# OPBS-Muscle.net
KiCad netlist of a schematic drawn in EAGLE
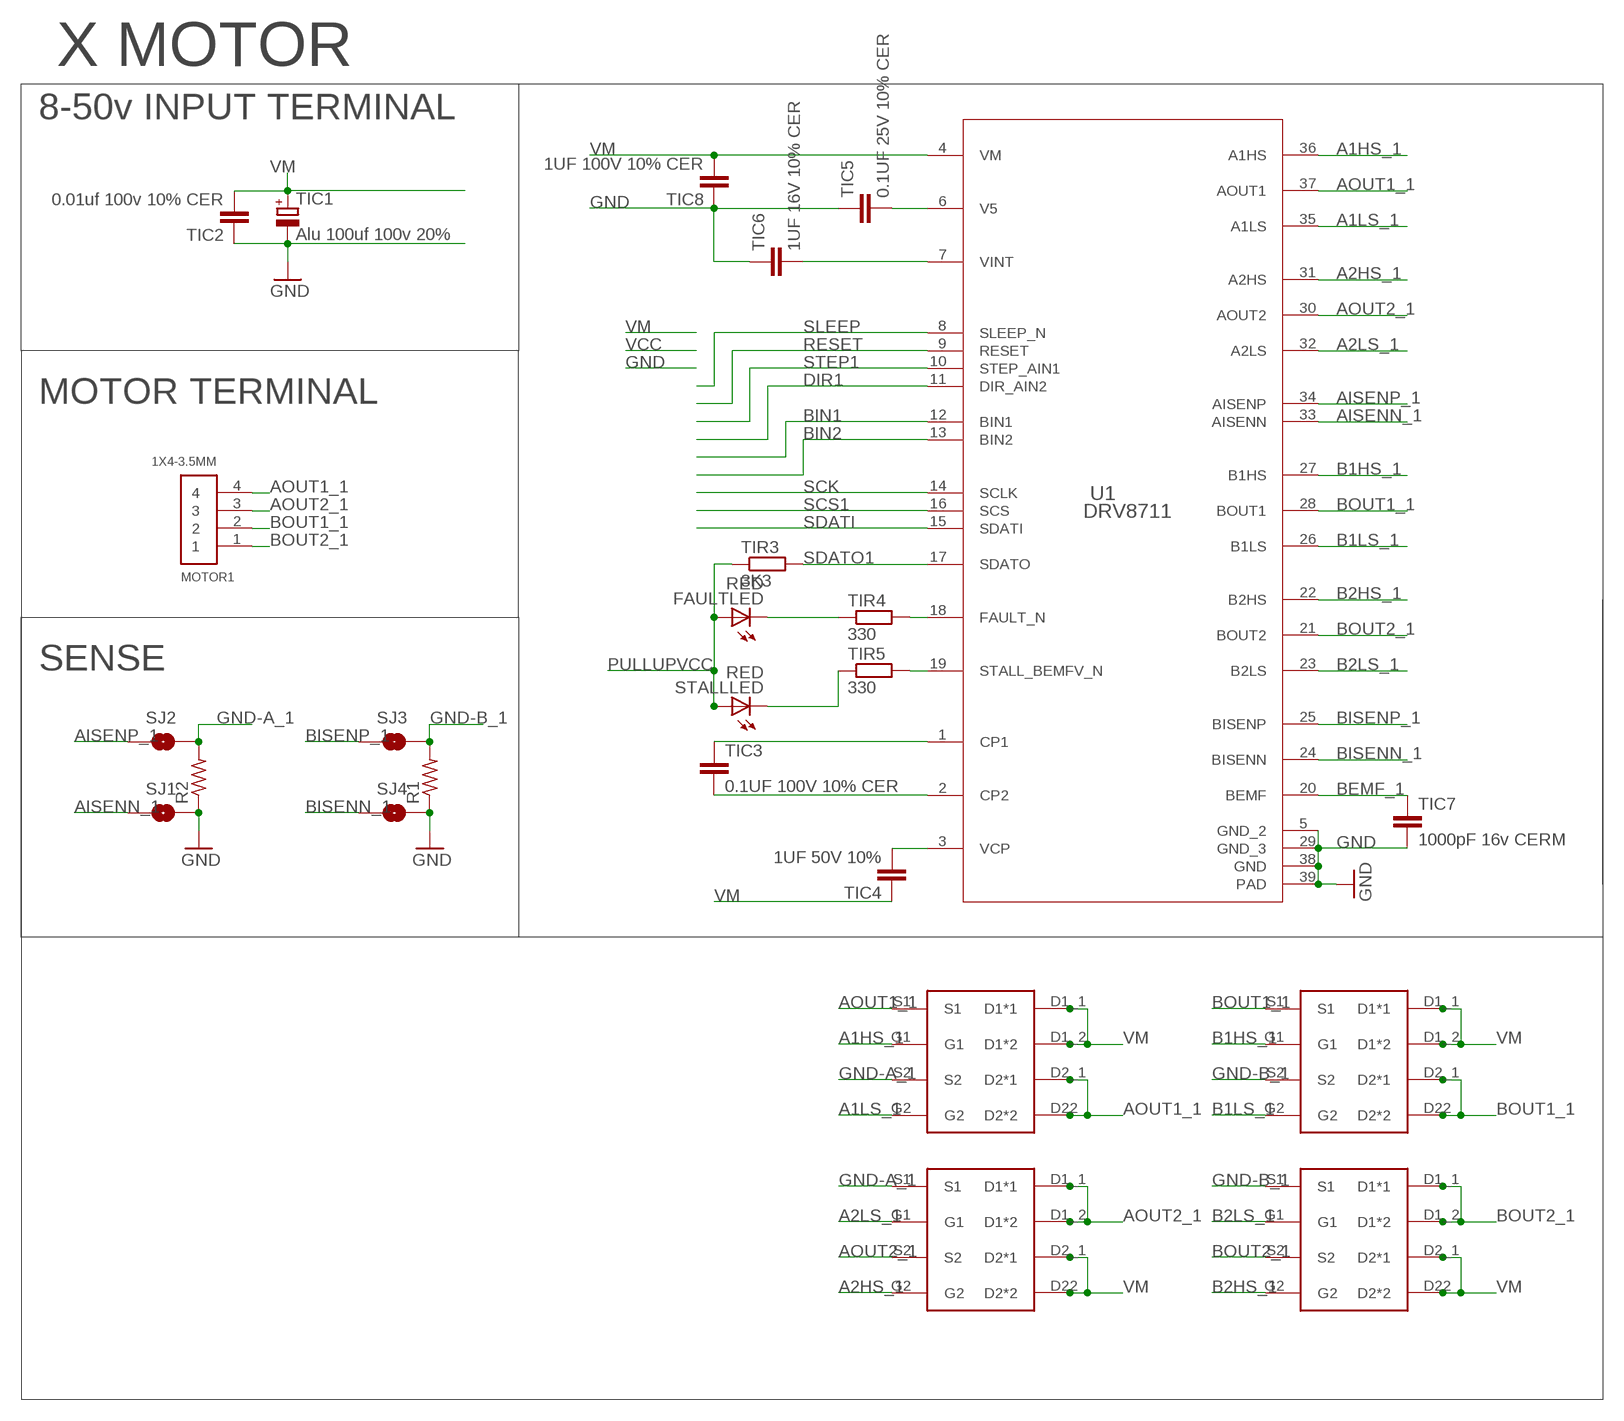
[diagram p0: schematic, sheet 1]
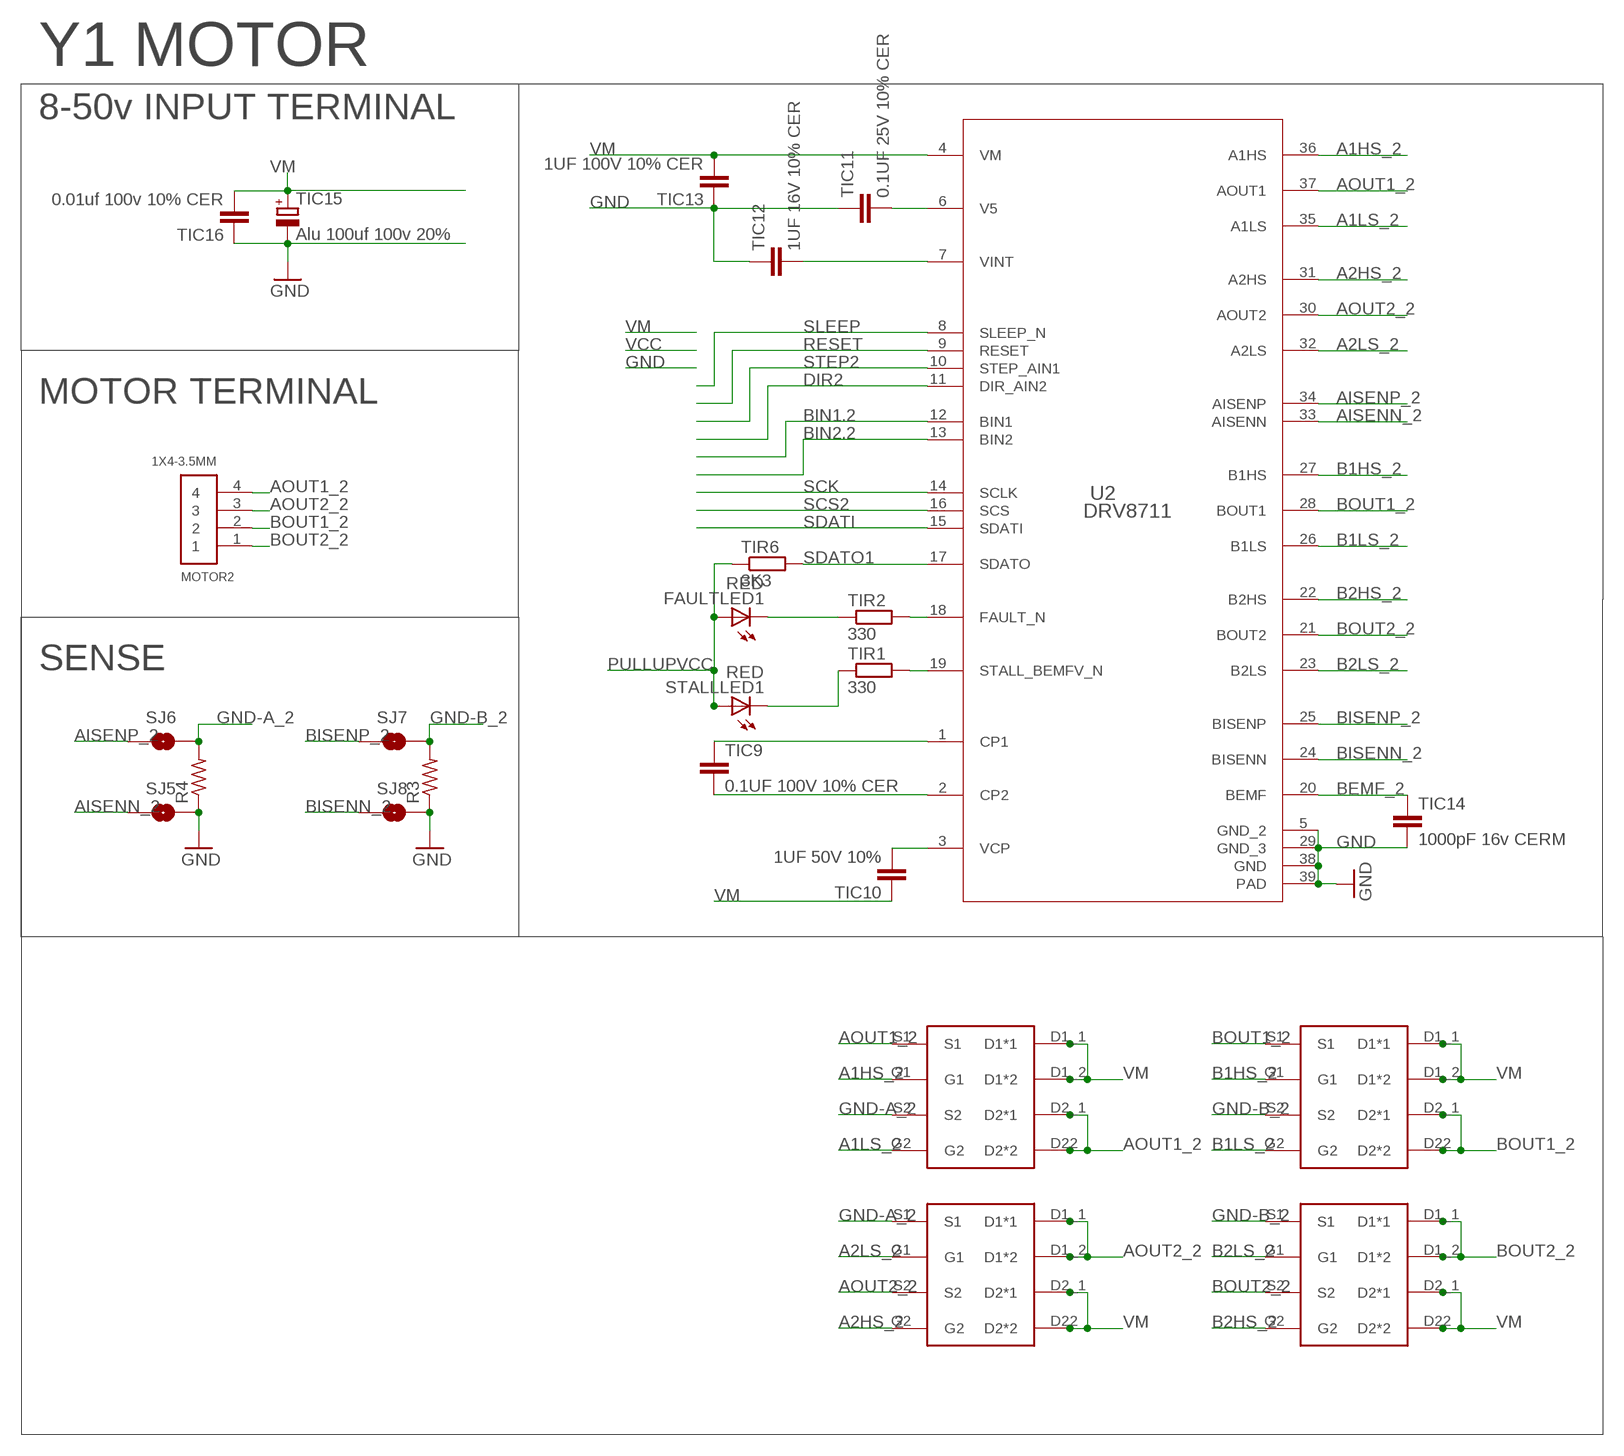
[diagram p1: schematic, sheet 2]
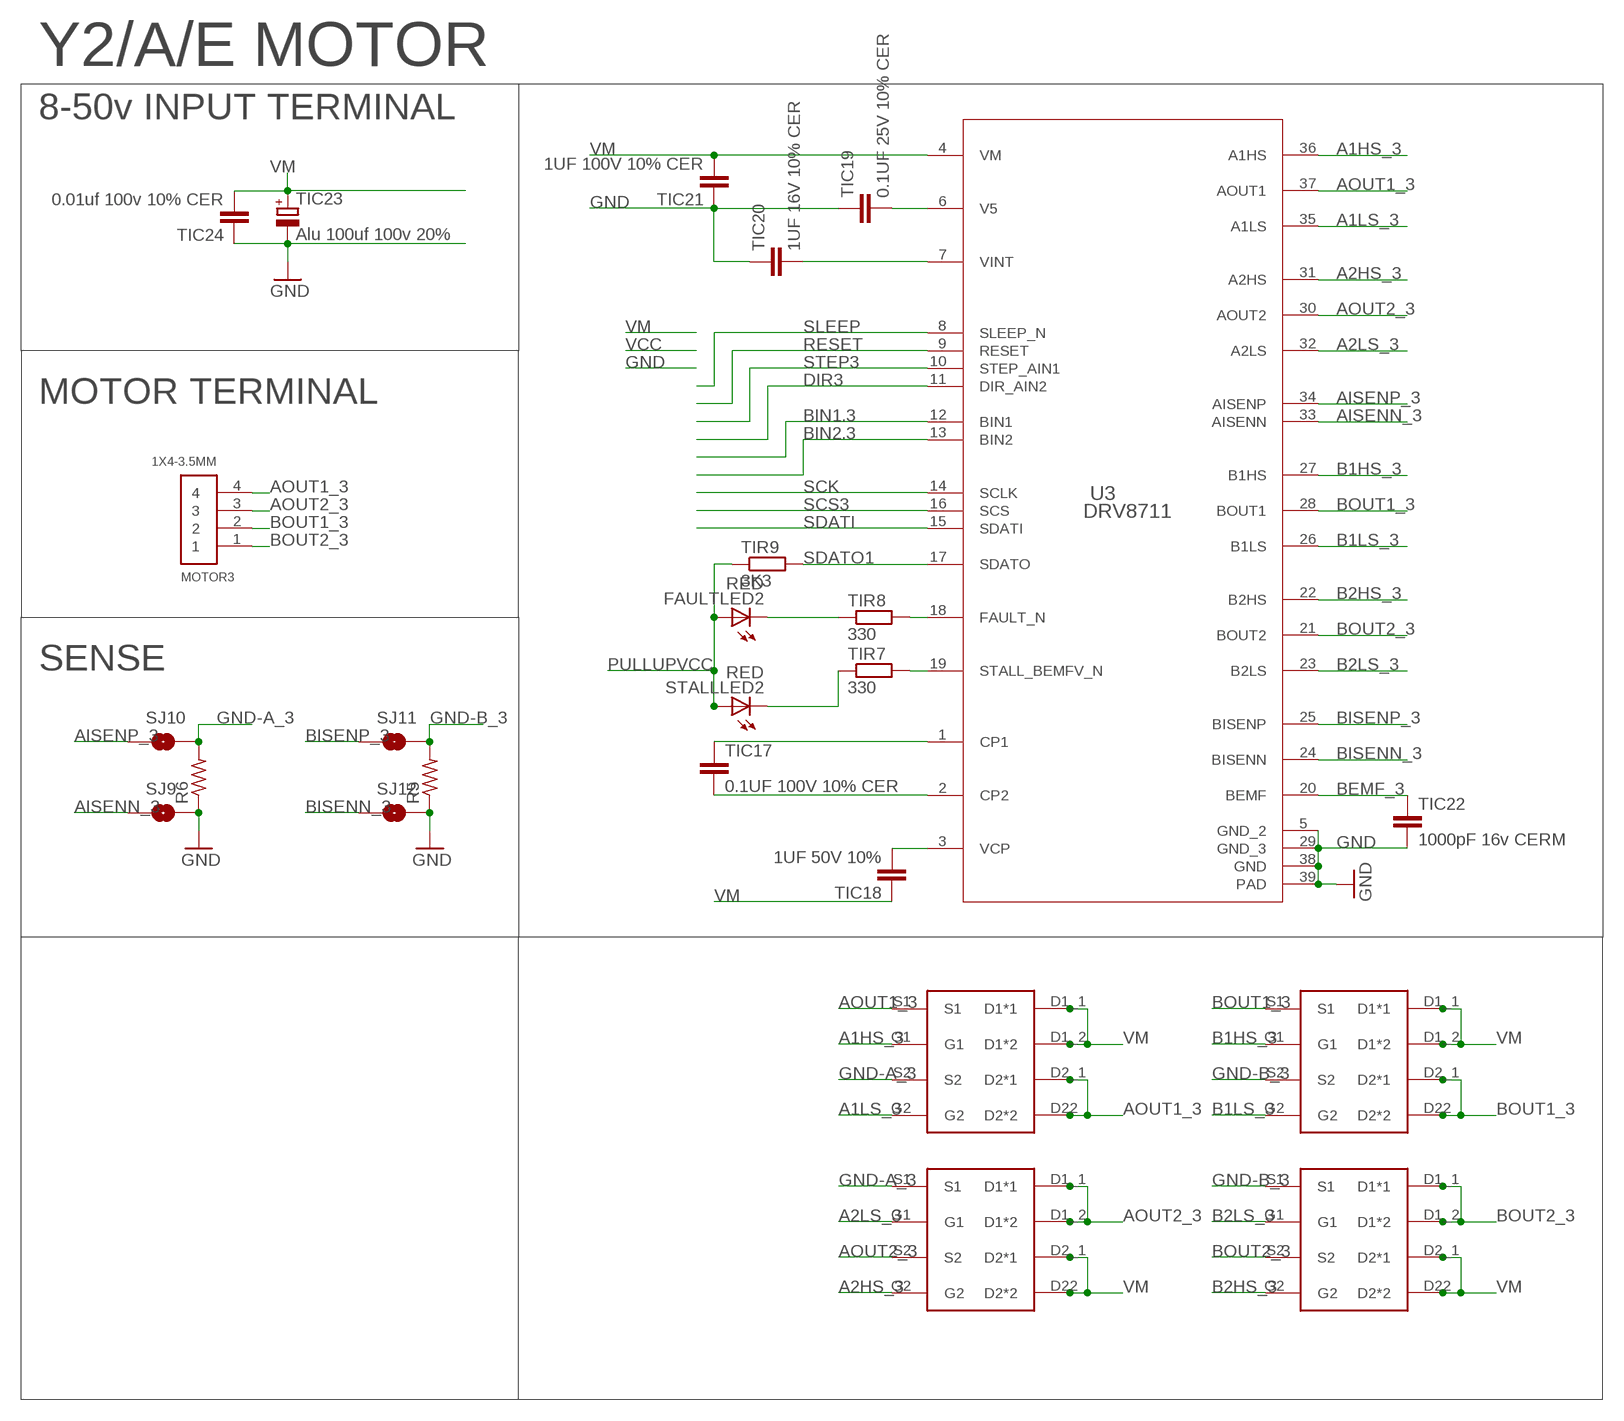
[diagram p2: schematic, sheet 3]
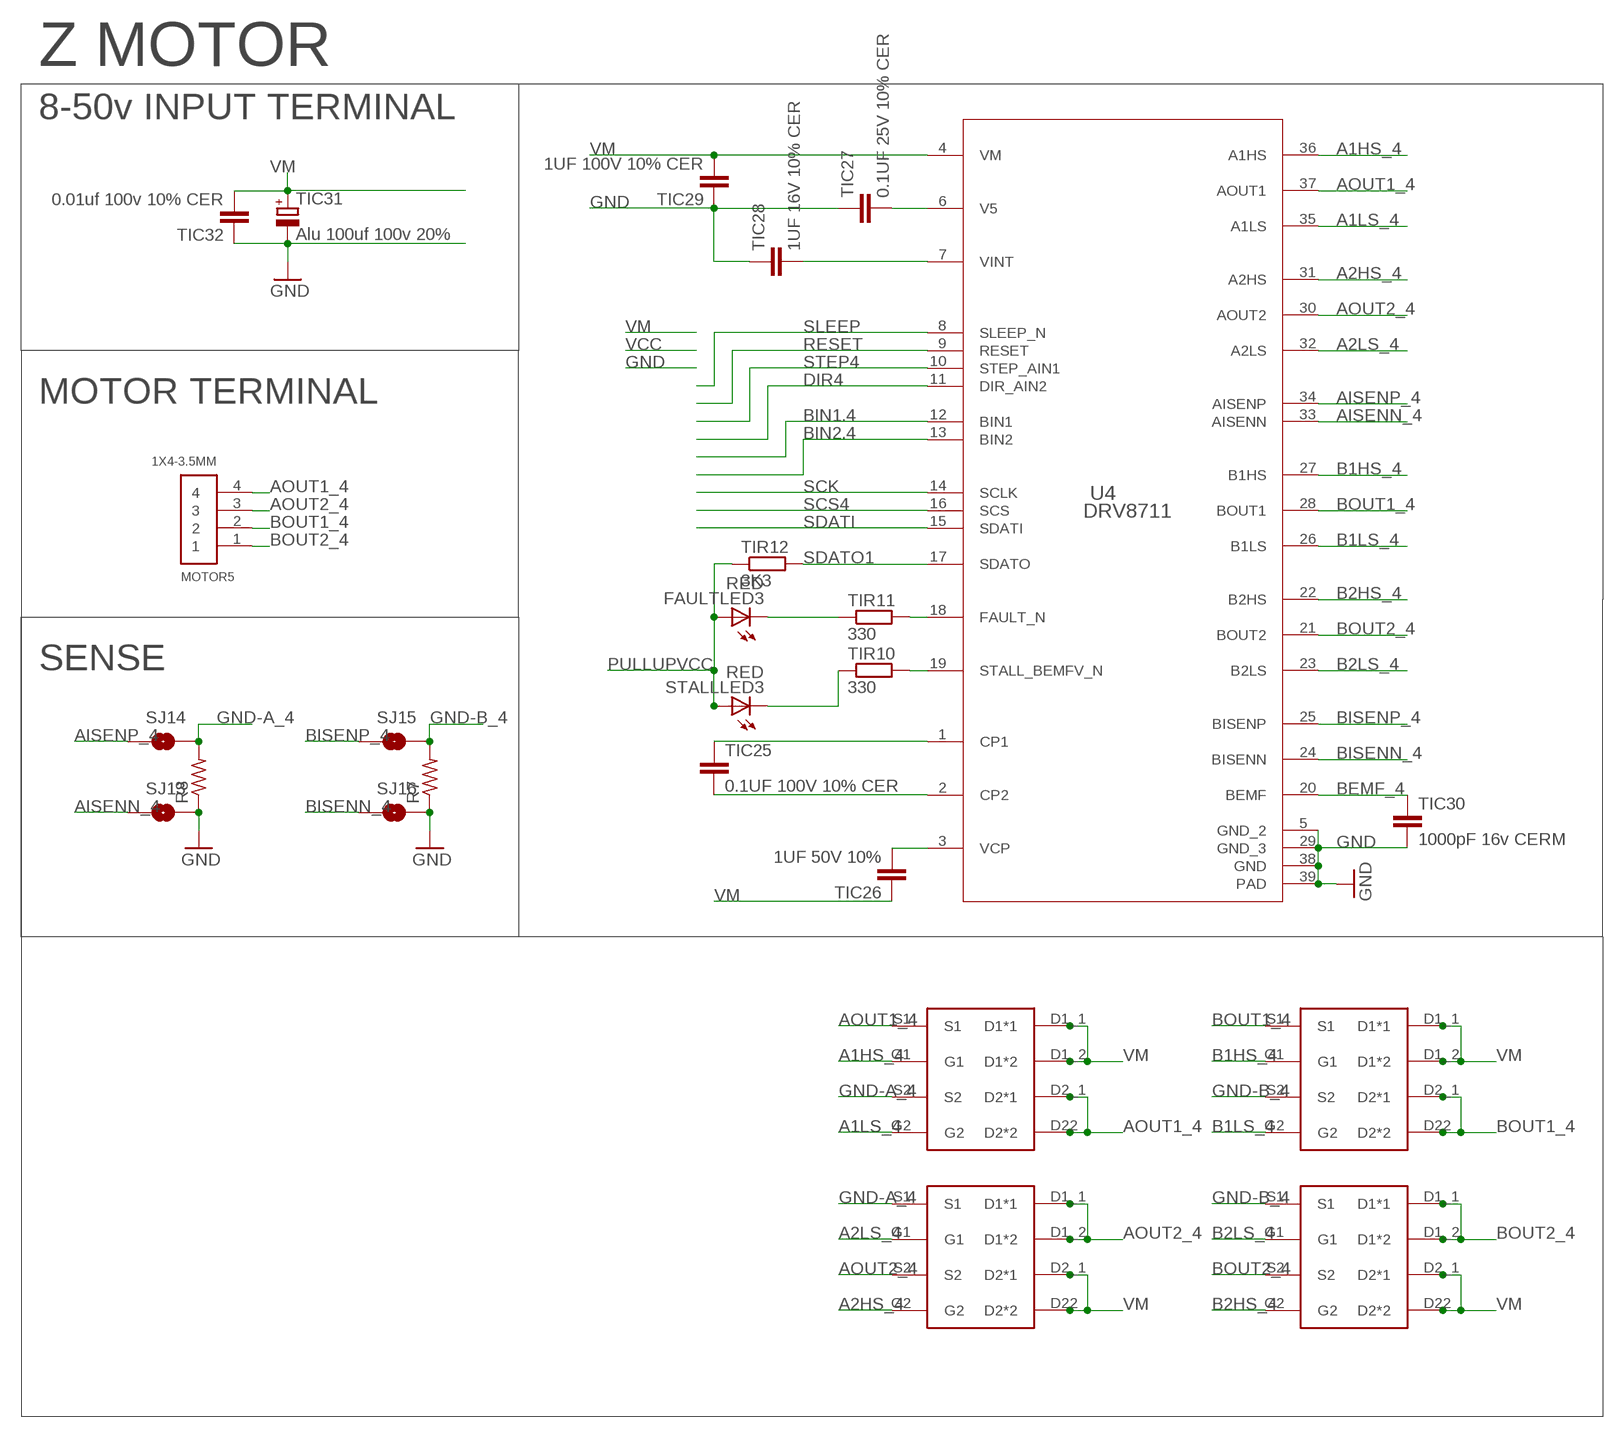
[diagram p3: schematic, sheet 4]
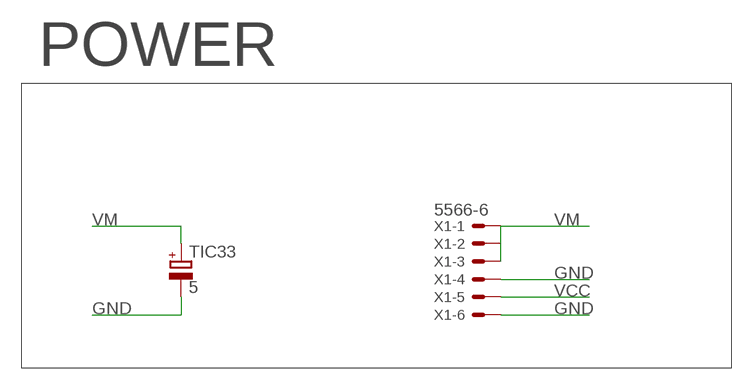
[diagram p4: schematic, sheet 5]
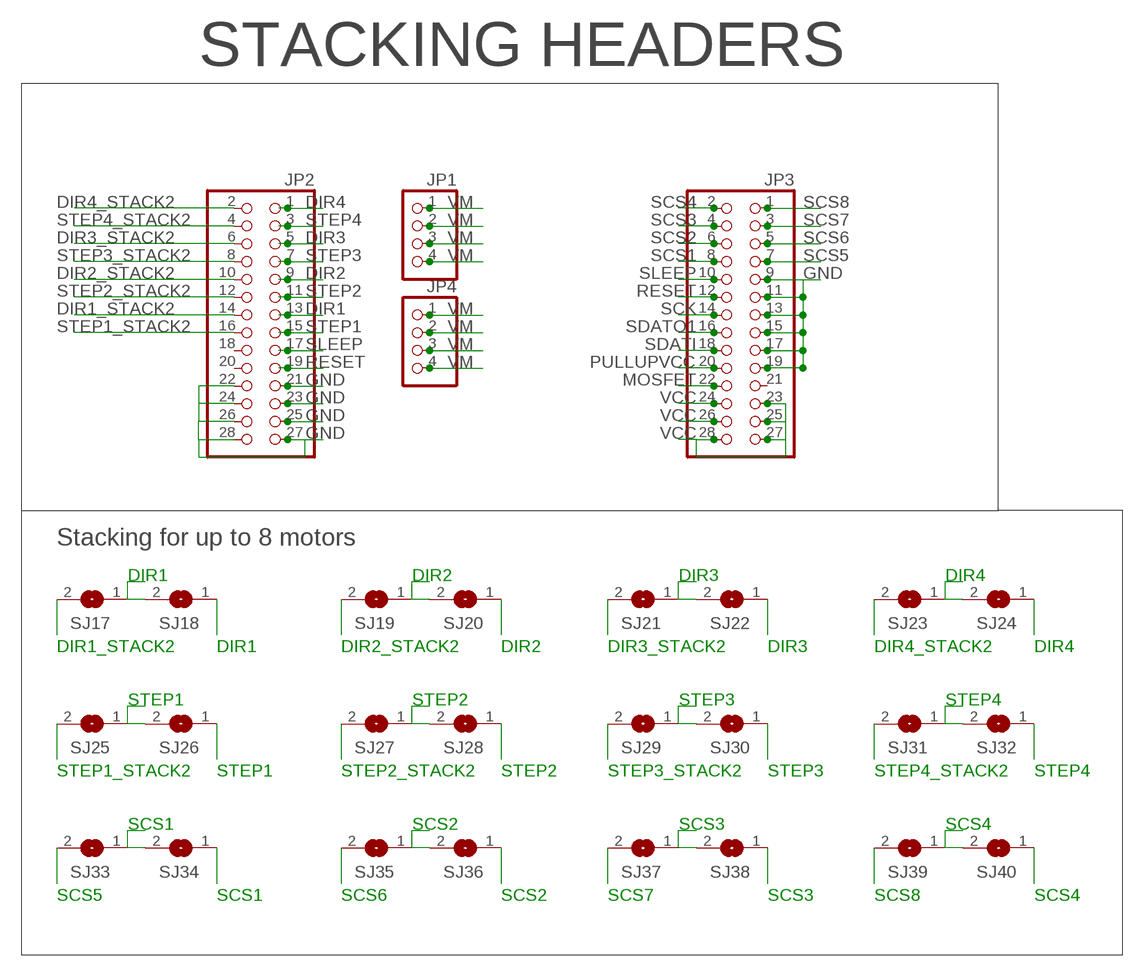
[diagram p5: schematic, sheet 6]
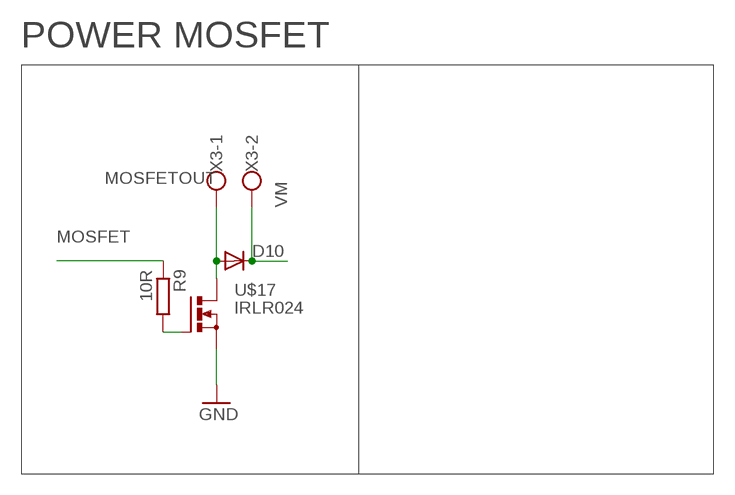
[diagram p6: schematic, sheet 7]

(export (version "E")
  (design (tool "Eeschema 10.0.6"))
  (components
    (comp (ref "FAULTLED2")
      (value "RED")
      (footprint "eagle-import:1206")
      (libsource (lib "eagle-import") (part "LEDSMT1206"))
    )
    (comp (ref "MOTOR3")
      (value "1X4-3.5MM")
      (footprint "eagle-import:1X04-3.5MM")
      (libsource (lib "eagle-import") (part "1X4-3.5MM"))
    )
    (comp (ref "R5")
      (value "R-US_R2512")
      (footprint "eagle-import:R2512")
      (libsource (lib "eagle-import") (part "R-US_R2512"))
    )
    (comp (ref "R6")
      (value "R-US_R2512")
      (footprint "eagle-import:R2512")
      (libsource (lib "eagle-import") (part "R-US_R2512"))
    )
    (comp (ref "SJ9")
      (value "SOLDERJUMPERTRACE")
      (footprint "eagle-import:SJ_2S-TRACE")
      (libsource (lib "eagle-import") (part "SOLDERJUMPERTRACE"))
    )
    (comp (ref "SJ10")
      (value "SOLDERJUMPERTRACE")
      (footprint "eagle-import:SJ_2S-TRACE")
      (libsource (lib "eagle-import") (part "SOLDERJUMPERTRACE"))
    )
    (comp (ref "SJ11")
      (value "SOLDERJUMPERTRACE")
      (footprint "eagle-import:SJ_2S-TRACE")
      (libsource (lib "eagle-import") (part "SOLDERJUMPERTRACE"))
    )
    (comp (ref "SJ12")
      (value "SOLDERJUMPERTRACE")
      (footprint "eagle-import:SJ_2S-TRACE")
      (libsource (lib "eagle-import") (part "SOLDERJUMPERTRACE"))
    )
    (comp (ref "STALLLED2")
      (value "RED")
      (footprint "eagle-import:1206")
      (libsource (lib "eagle-import") (part "LEDSMT1206"))
    )
    (comp (ref "TIC17")
      (value "0.1UF 100V 10% CER")
      (footprint "eagle-import:C0603K")
      (libsource (lib "eagle-import") (part "C-EUC0603K"))
    )
    (comp (ref "TIC18")
      (value "1UF 50V 10%")
      (footprint "eagle-import:C0805K")
      (libsource (lib "eagle-import") (part "C-EUC0805K"))
    )
    (comp (ref "TIC19")
      (value "0.1UF 25V 10% CER")
      (footprint "eagle-import:C0603K")
      (libsource (lib "eagle-import") (part "C-EUC0603K"))
    )
    (comp (ref "TIC20")
      (value "1UF 16V 10% CER")
      (footprint "eagle-import:C0603K")
      (libsource (lib "eagle-import") (part "C-EUC0603K"))
    )
    (comp (ref "TIC21")
      (value "1UF 100V 10% CER")
      (footprint "eagle-import:C1206K")
      (libsource (lib "eagle-import") (part "C-EUC1206K"))
    )
    (comp (ref "TIC22")
      (value "1000pF 16v CERM")
      (footprint "eagle-import:C0603K")
      (libsource (lib "eagle-import") (part "C-EUC0603K"))
    )
    (comp (ref "TIC23")
      (value "Alu 100uf 100v 20%")
      (footprint "eagle-import:E5-10,5")
      (libsource (lib "eagle-import") (part "CPOL-EUE5-10.5"))
    )
    (comp (ref "TIC24")
      (value "0.01uf 100v 10% CER")
      (footprint "eagle-import:C0603K")
      (libsource (lib "eagle-import") (part "C-EUC0603K"))
    )
    (comp (ref "TIR7")
      (value "330")
      (footprint "eagle-import:R1206")
      (libsource (lib "eagle-import") (part "R-EU_R1206"))
    )
    (comp (ref "TIR8")
      (value "330")
      (footprint "eagle-import:R1206")
      (libsource (lib "eagle-import") (part "R-EU_R1206"))
    )
    (comp (ref "TIR9")
      (value "3K3")
      (footprint "eagle-import:R1206")
      (libsource (lib "eagle-import") (part "R-EU_R1206"))
    )
    (comp (ref "U$9")
      (value "CSD88537ND")
      (footprint "eagle-import:CSD88537ND")
      (libsource (lib "eagle-import") (part "CSD88537ND"))
    )
    (comp (ref "U$10")
      (value "CSD88537ND")
      (footprint "eagle-import:CSD88537ND")
      (libsource (lib "eagle-import") (part "CSD88537ND"))
    )
    (comp (ref "U$11")
      (value "CSD88537ND")
      (footprint "eagle-import:CSD88537ND")
      (libsource (lib "eagle-import") (part "CSD88537ND"))
    )
    (comp (ref "U$12")
      (value "CSD88537ND")
      (footprint "eagle-import:CSD88537ND")
      (libsource (lib "eagle-import") (part "CSD88537ND"))
    )
    (comp (ref "U3")
      (value "DRV8711")
      (footprint "eagle-import:DCP0038A_N")
      (fields
        (field (name "ALTERNATEPARTNUMBER") "DRV8711DCP")
        (field (name "MANUFACTURER") "Texas Instruments")
        (field (name "PARTNUMBER") "DRV8711DCPR")
      )
      (libsource (lib "eagle-import") (part "DRV8711DCPR"))
    )
    (comp (ref "FAULTLED3")
      (value "RED")
      (footprint "eagle-import:1206")
      (libsource (lib "eagle-import") (part "LEDSMT1206"))
    )
    (comp (ref "MOTOR5")
      (value "1X4-3.5MM")
      (footprint "eagle-import:1X04-3.5MM")
      (libsource (lib "eagle-import") (part "1X4-3.5MM"))
    )
    (comp (ref "R7")
      (value "R-US_R2512")
      (footprint "eagle-import:R2512")
      (libsource (lib "eagle-import") (part "R-US_R2512"))
    )
    (comp (ref "R8")
      (value "R-US_R2512")
      (footprint "eagle-import:R2512")
      (libsource (lib "eagle-import") (part "R-US_R2512"))
    )
    (comp (ref "SJ13")
      (value "SOLDERJUMPERTRACE")
      (footprint "eagle-import:SJ_2S-TRACE")
      (libsource (lib "eagle-import") (part "SOLDERJUMPERTRACE"))
    )
    (comp (ref "SJ14")
      (value "SOLDERJUMPERTRACE")
      (footprint "eagle-import:SJ_2S-TRACE")
      (libsource (lib "eagle-import") (part "SOLDERJUMPERTRACE"))
    )
    (comp (ref "SJ15")
      (value "SOLDERJUMPERTRACE")
      (footprint "eagle-import:SJ_2S-TRACE")
      (libsource (lib "eagle-import") (part "SOLDERJUMPERTRACE"))
    )
    (comp (ref "SJ16")
      (value "SOLDERJUMPERTRACE")
      (footprint "eagle-import:SJ_2S-TRACE")
      (libsource (lib "eagle-import") (part "SOLDERJUMPERTRACE"))
    )
    (comp (ref "STALLLED3")
      (value "RED")
      (footprint "eagle-import:1206")
      (libsource (lib "eagle-import") (part "LEDSMT1206"))
    )
    (comp (ref "TIC25")
      (value "0.1UF 100V 10% CER")
      (footprint "eagle-import:C0603K")
      (libsource (lib "eagle-import") (part "C-EUC0603K"))
    )
    (comp (ref "TIC26")
      (value "1UF 50V 10%")
      (footprint "eagle-import:C0805K")
      (libsource (lib "eagle-import") (part "C-EUC0805K"))
    )
    (comp (ref "TIC27")
      (value "0.1UF 25V 10% CER")
      (footprint "eagle-import:C0603K")
      (libsource (lib "eagle-import") (part "C-EUC0603K"))
    )
    (comp (ref "TIC28")
      (value "1UF 16V 10% CER")
      (footprint "eagle-import:C0603K")
      (libsource (lib "eagle-import") (part "C-EUC0603K"))
    )
    (comp (ref "TIC29")
      (value "1UF 100V 10% CER")
      (footprint "eagle-import:C1206K")
      (libsource (lib "eagle-import") (part "C-EUC1206K"))
    )
    (comp (ref "TIC30")
      (value "1000pF 16v CERM")
      (footprint "eagle-import:C0603K")
      (libsource (lib "eagle-import") (part "C-EUC0603K"))
    )
    (comp (ref "TIC31")
      (value "Alu 100uf 100v 20%")
      (footprint "eagle-import:E5-10,5")
      (libsource (lib "eagle-import") (part "CPOL-EUE5-10.5"))
    )
    (comp (ref "TIC32")
      (value "0.01uf 100v 10% CER")
      (footprint "eagle-import:C0603K")
      (libsource (lib "eagle-import") (part "C-EUC0603K"))
    )
    (comp (ref "TIR10")
      (value "330")
      (footprint "eagle-import:R1206")
      (libsource (lib "eagle-import") (part "R-EU_R1206"))
    )
    (comp (ref "TIR11")
      (value "330")
      (footprint "eagle-import:R1206")
      (libsource (lib "eagle-import") (part "R-EU_R1206"))
    )
    (comp (ref "TIR12")
      (value "3K3")
      (footprint "eagle-import:R1206")
      (libsource (lib "eagle-import") (part "R-EU_R1206"))
    )
    (comp (ref "U$13")
      (value "CSD88537ND")
      (footprint "eagle-import:CSD88537ND")
      (libsource (lib "eagle-import") (part "CSD88537ND"))
    )
    (comp (ref "U$14")
      (value "CSD88537ND")
      (footprint "eagle-import:CSD88537ND")
      (libsource (lib "eagle-import") (part "CSD88537ND"))
    )
    (comp (ref "U$15")
      (value "CSD88537ND")
      (footprint "eagle-import:CSD88537ND")
      (libsource (lib "eagle-import") (part "CSD88537ND"))
    )
    (comp (ref "U$16")
      (value "CSD88537ND")
      (footprint "eagle-import:CSD88537ND")
      (libsource (lib "eagle-import") (part "CSD88537ND"))
    )
    (comp (ref "U4")
      (value "DRV8711")
      (footprint "eagle-import:DCP0038A_N")
      (fields
        (field (name "ALTERNATEPARTNUMBER") "DRV8711DCP")
        (field (name "MANUFACTURER") "Texas Instruments")
        (field (name "PARTNUMBER") "DRV8711DCPR")
      )
      (libsource (lib "eagle-import") (part "DRV8711DCPR"))
    )
    (comp (ref "FAULTLED")
      (value "RED")
      (footprint "eagle-import:1206")
      (libsource (lib "eagle-import") (part "LEDSMT1206"))
    )
    (comp (ref "MOTOR1")
      (value "1X4-3.5MM")
      (footprint "eagle-import:1X04-3.5MM")
      (libsource (lib "eagle-import") (part "1X4-3.5MM"))
    )
    (comp (ref "R1")
      (value "R-US_R2512")
      (footprint "eagle-import:R2512")
      (libsource (lib "eagle-import") (part "R-US_R2512"))
    )
    (comp (ref "R2")
      (value "R-US_R2512")
      (footprint "eagle-import:R2512")
      (libsource (lib "eagle-import") (part "R-US_R2512"))
    )
    (comp (ref "SJ1")
      (value "SOLDERJUMPERTRACE")
      (footprint "eagle-import:SJ_2S-TRACE")
      (libsource (lib "eagle-import") (part "SOLDERJUMPERTRACE"))
    )
    (comp (ref "SJ2")
      (value "SOLDERJUMPERTRACE")
      (footprint "eagle-import:SJ_2S-TRACE")
      (libsource (lib "eagle-import") (part "SOLDERJUMPERTRACE"))
    )
    (comp (ref "SJ3")
      (value "SOLDERJUMPERTRACE")
      (footprint "eagle-import:SJ_2S-TRACE")
      (libsource (lib "eagle-import") (part "SOLDERJUMPERTRACE"))
    )
    (comp (ref "SJ4")
      (value "SOLDERJUMPERTRACE")
      (footprint "eagle-import:SJ_2S-TRACE")
      (libsource (lib "eagle-import") (part "SOLDERJUMPERTRACE"))
    )
    (comp (ref "STALLLED")
      (value "RED")
      (footprint "eagle-import:1206")
      (libsource (lib "eagle-import") (part "LEDSMT1206"))
    )
    (comp (ref "TIC1")
      (value "Alu 100uf 100v 20%")
      (footprint "eagle-import:E5-10,5")
      (libsource (lib "eagle-import") (part "CPOL-EUE5-10.5"))
    )
    (comp (ref "TIC2")
      (value "0.01uf 100v 10% CER")
      (footprint "eagle-import:C0603K")
      (libsource (lib "eagle-import") (part "C-EUC0603K"))
    )
    (comp (ref "TIC3")
      (value "0.1UF 100V 10% CER")
      (footprint "eagle-import:C0603K")
      (libsource (lib "eagle-import") (part "C-EUC0603K"))
    )
    (comp (ref "TIC4")
      (value "1UF 50V 10%")
      (footprint "eagle-import:C0805K")
      (libsource (lib "eagle-import") (part "C-EUC0805K"))
    )
    (comp (ref "TIC5")
      (value "0.1UF 25V 10% CER")
      (footprint "eagle-import:C0603K")
      (libsource (lib "eagle-import") (part "C-EUC0603K"))
    )
    (comp (ref "TIC6")
      (value "1UF 16V 10% CER")
      (footprint "eagle-import:C0603K")
      (libsource (lib "eagle-import") (part "C-EUC0603K"))
    )
    (comp (ref "TIC7")
      (value "1000pF 16v CERM")
      (footprint "eagle-import:C0603K")
      (libsource (lib "eagle-import") (part "C-EUC0603K"))
    )
    (comp (ref "TIC8")
      (value "1UF 100V 10% CER")
      (footprint "eagle-import:C1206K")
      (libsource (lib "eagle-import") (part "C-EUC1206K"))
    )
    (comp (ref "TIR3")
      (value "3K3")
      (footprint "eagle-import:R1206")
      (libsource (lib "eagle-import") (part "R-EU_R1206"))
    )
    (comp (ref "TIR4")
      (value "330")
      (footprint "eagle-import:R1206")
      (libsource (lib "eagle-import") (part "R-EU_R1206"))
    )
    (comp (ref "TIR5")
      (value "330")
      (footprint "eagle-import:R1206")
      (libsource (lib "eagle-import") (part "R-EU_R1206"))
    )
    (comp (ref "U$1")
      (value "CSD88537ND")
      (footprint "eagle-import:CSD88537ND")
      (libsource (lib "eagle-import") (part "CSD88537ND"))
    )
    (comp (ref "U$2")
      (value "CSD88537ND")
      (footprint "eagle-import:CSD88537ND")
      (libsource (lib "eagle-import") (part "CSD88537ND"))
    )
    (comp (ref "U$3")
      (value "CSD88537ND")
      (footprint "eagle-import:CSD88537ND")
      (libsource (lib "eagle-import") (part "CSD88537ND"))
    )
    (comp (ref "U$4")
      (value "CSD88537ND")
      (footprint "eagle-import:CSD88537ND")
      (libsource (lib "eagle-import") (part "CSD88537ND"))
    )
    (comp (ref "U1")
      (value "DRV8711")
      (footprint "eagle-import:DCP0038A_N")
      (fields
        (field (name "ALTERNATEPARTNUMBER") "DRV8711DCP")
        (field (name "MANUFACTURER") "Texas Instruments")
        (field (name "PARTNUMBER") "DRV8711DCPR")
      )
      (libsource (lib "eagle-import") (part "DRV8711DCPR"))
    )
    (comp (ref "D10")
      (value "DIODESMA-ALT")
      (footprint "eagle-import:SMA-DIODE_ALT")
      (libsource (lib "eagle-import") (part "DIODESMA-ALT"))
    )
    (comp (ref "R9")
      (value "10R")
      (footprint "eagle-import:M1206")
      (libsource (lib "eagle-import") (part "resistor_R-EU_M1206"))
    )
    (comp (ref "U$17")
      (value "IRLR024")
      (footprint "eagle-import:D-PAK_TO252AA")
      (libsource (lib "eagle-import") (part "IRLR024"))
    )
    (comp (ref "X3")
      (value "W237-102")
      (footprint "eagle-import:W237-102")
      (fields (field (name "MPN") "237-102"))
      (libsource (lib "eagle-import") (part "W237-102"))
    )
    (comp (ref "JP1")
      (value "PINHD-1X4")
      (footprint "eagle-import:1X04")
      (libsource (lib "eagle-import") (part "PINHD-1X4"))
    )
    (comp (ref "JP2")
      (value "PINHD-2X14")
      (footprint "eagle-import:2X14")
      (libsource (lib "eagle-import") (part "PINHD-2X14"))
    )
    (comp (ref "JP3")
      (value "PINHD-2X14")
      (footprint "eagle-import:2X14")
      (libsource (lib "eagle-import") (part "PINHD-2X14"))
    )
    (comp (ref "JP4")
      (value "PINHD-1X4")
      (footprint "eagle-import:1X04")
      (libsource (lib "eagle-import") (part "PINHD-1X4"))
    )
    (comp (ref "SJ17")
      (value "SJ")
      (footprint "eagle-import:SJ")
      (libsource (lib "eagle-import") (part "SJ"))
    )
    (comp (ref "SJ18")
      (value "SJ")
      (footprint "eagle-import:SJ")
      (libsource (lib "eagle-import") (part "SJ"))
    )
    (comp (ref "SJ19")
      (value "SJ")
      (footprint "eagle-import:SJ")
      (libsource (lib "eagle-import") (part "SJ"))
    )
    (comp (ref "SJ20")
      (value "SJ")
      (footprint "eagle-import:SJ")
      (libsource (lib "eagle-import") (part "SJ"))
    )
    (comp (ref "SJ21")
      (value "SJ")
      (footprint "eagle-import:SJ")
      (libsource (lib "eagle-import") (part "SJ"))
    )
    (comp (ref "SJ22")
      (value "SJ")
      (footprint "eagle-import:SJ")
      (libsource (lib "eagle-import") (part "SJ"))
    )
    (comp (ref "SJ23")
      (value "SJ")
      (footprint "eagle-import:SJ")
      (libsource (lib "eagle-import") (part "SJ"))
    )
    (comp (ref "SJ24")
      (value "SJ")
      (footprint "eagle-import:SJ")
      (libsource (lib "eagle-import") (part "SJ"))
    )
    (comp (ref "SJ25")
      (value "SJ")
      (footprint "eagle-import:SJ")
      (libsource (lib "eagle-import") (part "SJ"))
    )
    (comp (ref "SJ26")
      (value "SJ")
      (footprint "eagle-import:SJ")
      (libsource (lib "eagle-import") (part "SJ"))
    )
    (comp (ref "SJ27")
      (value "SJ")
      (footprint "eagle-import:SJ")
      (libsource (lib "eagle-import") (part "SJ"))
    )
    (comp (ref "SJ28")
      (value "SJ")
      (footprint "eagle-import:SJ")
      (libsource (lib "eagle-import") (part "SJ"))
    )
    (comp (ref "SJ29")
      (value "SJ")
      (footprint "eagle-import:SJ")
      (libsource (lib "eagle-import") (part "SJ"))
    )
    (comp (ref "SJ30")
      (value "SJ")
      (footprint "eagle-import:SJ")
      (libsource (lib "eagle-import") (part "SJ"))
    )
    (comp (ref "SJ31")
      (value "SJ")
      (footprint "eagle-import:SJ")
      (libsource (lib "eagle-import") (part "SJ"))
    )
    (comp (ref "SJ32")
      (value "SJ")
      (footprint "eagle-import:SJ")
      (libsource (lib "eagle-import") (part "SJ"))
    )
    (comp (ref "SJ33")
      (value "SJ")
      (footprint "eagle-import:SJ")
      (libsource (lib "eagle-import") (part "SJ"))
    )
    (comp (ref "SJ34")
      (value "SJ")
      (footprint "eagle-import:SJ")
      (libsource (lib "eagle-import") (part "SJ"))
    )
    (comp (ref "SJ35")
      (value "SJ")
      (footprint "eagle-import:SJ")
      (libsource (lib "eagle-import") (part "SJ"))
    )
    (comp (ref "SJ36")
      (value "SJ")
      (footprint "eagle-import:SJ")
      (libsource (lib "eagle-import") (part "SJ"))
    )
    (comp (ref "SJ37")
      (value "SJ")
      (footprint "eagle-import:SJ")
      (libsource (lib "eagle-import") (part "SJ"))
    )
    (comp (ref "SJ38")
      (value "SJ")
      (footprint "eagle-import:SJ")
      (libsource (lib "eagle-import") (part "SJ"))
    )
    (comp (ref "SJ39")
      (value "SJ")
      (footprint "eagle-import:SJ")
      (libsource (lib "eagle-import") (part "SJ"))
    )
    (comp (ref "SJ40")
      (value "SJ")
      (footprint "eagle-import:SJ")
      (libsource (lib "eagle-import") (part "SJ"))
    )
    (comp (ref "TIC33")
      (value "5")
      (footprint "eagle-import:E5-10,5")
      (libsource (lib "eagle-import") (part "CPOL-EUE5-10.5"))
    )
    (comp (ref "X1")
      (value "5566-6")
      (footprint "eagle-import:5566-6")
      (fields (field (name "MPN") "95566-61002"))
      (libsource (lib "eagle-import") (part "5566-6"))
    )
    (comp (ref "FAULTLED1")
      (value "RED")
      (footprint "eagle-import:1206")
      (libsource (lib "eagle-import") (part "LEDSMT1206"))
    )
    (comp (ref "MOTOR2")
      (value "1X4-3.5MM")
      (footprint "eagle-import:1X04-3.5MM")
      (libsource (lib "eagle-import") (part "1X4-3.5MM"))
    )
    (comp (ref "R3")
      (value "R-US_R2512")
      (footprint "eagle-import:R2512")
      (libsource (lib "eagle-import") (part "R-US_R2512"))
    )
    (comp (ref "R4")
      (value "R-US_R2512")
      (footprint "eagle-import:R2512")
      (libsource (lib "eagle-import") (part "R-US_R2512"))
    )
    (comp (ref "SJ5")
      (value "SOLDERJUMPERTRACE")
      (footprint "eagle-import:SJ_2S-TRACE")
      (libsource (lib "eagle-import") (part "SOLDERJUMPERTRACE"))
    )
    (comp (ref "SJ6")
      (value "SOLDERJUMPERTRACE")
      (footprint "eagle-import:SJ_2S-TRACE")
      (libsource (lib "eagle-import") (part "SOLDERJUMPERTRACE"))
    )
    (comp (ref "SJ7")
      (value "SOLDERJUMPERTRACE")
      (footprint "eagle-import:SJ_2S-TRACE")
      (libsource (lib "eagle-import") (part "SOLDERJUMPERTRACE"))
    )
    (comp (ref "SJ8")
      (value "SOLDERJUMPERTRACE")
      (footprint "eagle-import:SJ_2S-TRACE")
      (libsource (lib "eagle-import") (part "SOLDERJUMPERTRACE"))
    )
    (comp (ref "STALLLED1")
      (value "RED")
      (footprint "eagle-import:1206")
      (libsource (lib "eagle-import") (part "LEDSMT1206"))
    )
    (comp (ref "TIC9")
      (value "0.1UF 100V 10% CER")
      (footprint "eagle-import:C0603K")
      (libsource (lib "eagle-import") (part "C-EUC0603K"))
    )
    (comp (ref "TIC10")
      (value "1UF 50V 10%")
      (footprint "eagle-import:C0805K")
      (libsource (lib "eagle-import") (part "C-EUC0805K"))
    )
    (comp (ref "TIC11")
      (value "0.1UF 25V 10% CER")
      (footprint "eagle-import:C0603K")
      (libsource (lib "eagle-import") (part "C-EUC0603K"))
    )
    (comp (ref "TIC12")
      (value "1UF 16V 10% CER")
      (footprint "eagle-import:C0603K")
      (libsource (lib "eagle-import") (part "C-EUC0603K"))
    )
    (comp (ref "TIC13")
      (value "1UF 100V 10% CER")
      (footprint "eagle-import:C1206K")
      (libsource (lib "eagle-import") (part "C-EUC1206K"))
    )
    (comp (ref "TIC14")
      (value "1000pF 16v CERM")
      (footprint "eagle-import:C0603K")
      (libsource (lib "eagle-import") (part "C-EUC0603K"))
    )
    (comp (ref "TIC15")
      (value "Alu 100uf 100v 20%")
      (footprint "eagle-import:E5-10,5")
      (libsource (lib "eagle-import") (part "CPOL-EUE5-10.5"))
    )
    (comp (ref "TIC16")
      (value "0.01uf 100v 10% CER")
      (footprint "eagle-import:C0603K")
      (libsource (lib "eagle-import") (part "C-EUC0603K"))
    )
    (comp (ref "TIR1")
      (value "330")
      (footprint "eagle-import:R1206")
      (libsource (lib "eagle-import") (part "R-EU_R1206"))
    )
    (comp (ref "TIR2")
      (value "330")
      (footprint "eagle-import:R1206")
      (libsource (lib "eagle-import") (part "R-EU_R1206"))
    )
    (comp (ref "TIR6")
      (value "3K3")
      (footprint "eagle-import:R1206")
      (libsource (lib "eagle-import") (part "R-EU_R1206"))
    )
    (comp (ref "U$5")
      (value "CSD88537ND")
      (footprint "eagle-import:CSD88537ND")
      (libsource (lib "eagle-import") (part "CSD88537ND"))
    )
    (comp (ref "U$6")
      (value "CSD88537ND")
      (footprint "eagle-import:CSD88537ND")
      (libsource (lib "eagle-import") (part "CSD88537ND"))
    )
    (comp (ref "U$7")
      (value "CSD88537ND")
      (footprint "eagle-import:CSD88537ND")
      (libsource (lib "eagle-import") (part "CSD88537ND"))
    )
    (comp (ref "U$8")
      (value "CSD88537ND")
      (footprint "eagle-import:CSD88537ND")
      (libsource (lib "eagle-import") (part "CSD88537ND"))
    )
    (comp (ref "U2")
      (value "DRV8711")
      (footprint "eagle-import:DCP0038A_N")
      (fields
        (field (name "ALTERNATEPARTNUMBER") "DRV8711DCP")
        (field (name "MANUFACTURER") "Texas Instruments")
        (field (name "PARTNUMBER") "DRV8711DCPR")
      )
      (libsource (lib "eagle-import") (part "DRV8711DCPR"))
    )
  )
  (nets
    (net (code "1") (name "A1HS_1") (class "Default")
      (node (ref "U$1") (pin "G1") (pinfunction "G1_G1") (pintype "power_in"))
      (node (ref "U1") (pin "36") (pinfunction "A1HS_36") (pintype "output"))
    )
    (net (code "2") (name "A1HS_2") (class "Default")
      (node (ref "U$5") (pin "G1") (pinfunction "G1_G1") (pintype "power_in"))
      (node (ref "U2") (pin "36") (pinfunction "A1HS_36") (pintype "output"))
    )
    (net (code "3") (name "A1HS_3") (class "Default")
      (node (ref "U$9") (pin "G1") (pinfunction "G1_G1") (pintype "power_in"))
      (node (ref "U3") (pin "36") (pinfunction "A1HS_36") (pintype "output"))
    )
    (net (code "4") (name "A1HS_4") (class "Default")
      (node (ref "U$13") (pin "G1") (pinfunction "G1_G1") (pintype "power_in"))
      (node (ref "U4") (pin "36") (pinfunction "A1HS_36") (pintype "output"))
    )
    (net (code "5") (name "A1LS_1") (class "Default")
      (node (ref "U$1") (pin "G2") (pinfunction "G2_G2") (pintype "power_in"))
      (node (ref "U1") (pin "35") (pinfunction "A1LS_35") (pintype "output"))
    )
    (net (code "6") (name "A1LS_2") (class "Default")
      (node (ref "U$5") (pin "G2") (pinfunction "G2_G2") (pintype "power_in"))
      (node (ref "U2") (pin "35") (pinfunction "A1LS_35") (pintype "output"))
    )
    (net (code "7") (name "A1LS_3") (class "Default")
      (node (ref "U$9") (pin "G2") (pinfunction "G2_G2") (pintype "power_in"))
      (node (ref "U3") (pin "35") (pinfunction "A1LS_35") (pintype "output"))
    )
    (net (code "8") (name "A1LS_4") (class "Default")
      (node (ref "U$13") (pin "G2") (pinfunction "G2_G2") (pintype "power_in"))
      (node (ref "U4") (pin "35") (pinfunction "A1LS_35") (pintype "output"))
    )
    (net (code "9") (name "A2HS_1") (class "Default")
      (node (ref "U$3") (pin "G2") (pinfunction "G2_G2") (pintype "power_in"))
      (node (ref "U1") (pin "31") (pinfunction "A2HS_31") (pintype "output"))
    )
    (net (code "10") (name "A2HS_2") (class "Default")
      (node (ref "U$7") (pin "G2") (pinfunction "G2_G2") (pintype "power_in"))
      (node (ref "U2") (pin "31") (pinfunction "A2HS_31") (pintype "output"))
    )
    (net (code "11") (name "A2HS_3") (class "Default")
      (node (ref "U$11") (pin "G2") (pinfunction "G2_G2") (pintype "power_in"))
      (node (ref "U3") (pin "31") (pinfunction "A2HS_31") (pintype "output"))
    )
    (net (code "12") (name "A2HS_4") (class "Default")
      (node (ref "U$15") (pin "G2") (pinfunction "G2_G2") (pintype "power_in"))
      (node (ref "U4") (pin "31") (pinfunction "A2HS_31") (pintype "output"))
    )
    (net (code "13") (name "A2LS_1") (class "Default")
      (node (ref "U$3") (pin "G1") (pinfunction "G1_G1") (pintype "power_in"))
      (node (ref "U1") (pin "32") (pinfunction "A2LS_32") (pintype "output"))
    )
    (net (code "14") (name "A2LS_2") (class "Default")
      (node (ref "U$7") (pin "G1") (pinfunction "G1_G1") (pintype "power_in"))
      (node (ref "U2") (pin "32") (pinfunction "A2LS_32") (pintype "output"))
    )
    (net (code "15") (name "A2LS_3") (class "Default")
      (node (ref "U$11") (pin "G1") (pinfunction "G1_G1") (pintype "power_in"))
      (node (ref "U3") (pin "32") (pinfunction "A2LS_32") (pintype "output"))
    )
    (net (code "16") (name "A2LS_4") (class "Default")
      (node (ref "U$15") (pin "G1") (pinfunction "G1_G1") (pintype "power_in"))
      (node (ref "U4") (pin "32") (pinfunction "A2LS_32") (pintype "output"))
    )
    (net (code "17") (name "AISENN_1") (class "Default")
      (node (ref "SJ1") (pin "1") (pinfunction "1_1") (pintype "passive"))
      (node (ref "U1") (pin "33") (pinfunction "AISENN_33") (pintype "input"))
    )
    (net (code "18") (name "AISENN_2") (class "Default")
      (node (ref "SJ5") (pin "1") (pinfunction "1_1") (pintype "passive"))
      (node (ref "U2") (pin "33") (pinfunction "AISENN_33") (pintype "input"))
    )
    (net (code "19") (name "AISENN_3") (class "Default")
      (node (ref "SJ9") (pin "1") (pinfunction "1_1") (pintype "passive"))
      (node (ref "U3") (pin "33") (pinfunction "AISENN_33") (pintype "input"))
    )
    (net (code "20") (name "AISENN_4") (class "Default")
      (node (ref "SJ13") (pin "1") (pinfunction "1_1") (pintype "passive"))
      (node (ref "U4") (pin "33") (pinfunction "AISENN_33") (pintype "input"))
    )
    (net (code "21") (name "AISENP_1") (class "Default")
      (node (ref "SJ2") (pin "1") (pinfunction "1_1") (pintype "passive"))
      (node (ref "U1") (pin "34") (pinfunction "AISENP_34") (pintype "input"))
    )
    (net (code "22") (name "AISENP_2") (class "Default")
      (node (ref "SJ6") (pin "1") (pinfunction "1_1") (pintype "passive"))
      (node (ref "U2") (pin "34") (pinfunction "AISENP_34") (pintype "input"))
    )
    (net (code "23") (name "AISENP_3") (class "Default")
      (node (ref "SJ10") (pin "1") (pinfunction "1_1") (pintype "passive"))
      (node (ref "U3") (pin "34") (pinfunction "AISENP_34") (pintype "input"))
    )
    (net (code "24") (name "AISENP_4") (class "Default")
      (node (ref "SJ14") (pin "1") (pinfunction "1_1") (pintype "passive"))
      (node (ref "U4") (pin "34") (pinfunction "AISENP_34") (pintype "input"))
    )
    (net (code "25") (name "AOUT1_1") (class "Default")
      (node (ref "MOTOR1") (pin "4") (pinfunction "4_4") (pintype "bidirectional"))
      (node (ref "U$1") (pin "D22") (pinfunction "D2*2_D22") (pintype "power_in"))
      (node (ref "U$1") (pin "D2_1") (pinfunction "D2*1_D2_1") (pintype "power_in"))
      (node (ref "U$1") (pin "S1") (pinfunction "S1_S1") (pintype "power_in"))
      (node (ref "U1") (pin "37") (pinfunction "AOUT1_37") (pintype "output"))
    )
    (net (code "26") (name "AOUT1_2") (class "Default")
      (node (ref "MOTOR2") (pin "4") (pinfunction "4_4") (pintype "bidirectional"))
      (node (ref "U$5") (pin "D22") (pinfunction "D2*2_D22") (pintype "power_in"))
      (node (ref "U$5") (pin "D2_1") (pinfunction "D2*1_D2_1") (pintype "power_in"))
      (node (ref "U$5") (pin "S1") (pinfunction "S1_S1") (pintype "power_in"))
      (node (ref "U2") (pin "37") (pinfunction "AOUT1_37") (pintype "output"))
    )
    (net (code "27") (name "AOUT1_3") (class "Default")
      (node (ref "MOTOR3") (pin "4") (pinfunction "4_4") (pintype "bidirectional"))
      (node (ref "U$9") (pin "D22") (pinfunction "D2*2_D22") (pintype "power_in"))
      (node (ref "U$9") (pin "D2_1") (pinfunction "D2*1_D2_1") (pintype "power_in"))
      (node (ref "U$9") (pin "S1") (pinfunction "S1_S1") (pintype "power_in"))
      (node (ref "U3") (pin "37") (pinfunction "AOUT1_37") (pintype "output"))
    )
    (net (code "28") (name "AOUT1_4") (class "Default")
      (node (ref "MOTOR5") (pin "4") (pinfunction "4_4") (pintype "bidirectional"))
      (node (ref "U$13") (pin "D22") (pinfunction "D2*2_D22") (pintype "power_in"))
      (node (ref "U$13") (pin "D2_1") (pinfunction "D2*1_D2_1") (pintype "power_in"))
      (node (ref "U$13") (pin "S1") (pinfunction "S1_S1") (pintype "power_in"))
      (node (ref "U4") (pin "37") (pinfunction "AOUT1_37") (pintype "output"))
    )
    (net (code "29") (name "AOUT2_1") (class "Default")
      (node (ref "MOTOR1") (pin "3") (pinfunction "3_3") (pintype "bidirectional"))
      (node (ref "U$3") (pin "D1_1") (pinfunction "D1*1_D1_1") (pintype "power_in"))
      (node (ref "U$3") (pin "D1_2") (pinfunction "D1*2_D1_2") (pintype "power_in"))
      (node (ref "U$3") (pin "S2") (pinfunction "S2_S2") (pintype "power_in"))
      (node (ref "U1") (pin "30") (pinfunction "AOUT2_30") (pintype "output"))
    )
    (net (code "30") (name "AOUT2_2") (class "Default")
      (node (ref "MOTOR2") (pin "3") (pinfunction "3_3") (pintype "bidirectional"))
      (node (ref "U$7") (pin "D1_1") (pinfunction "D1*1_D1_1") (pintype "power_in"))
      (node (ref "U$7") (pin "D1_2") (pinfunction "D1*2_D1_2") (pintype "power_in"))
      (node (ref "U$7") (pin "S2") (pinfunction "S2_S2") (pintype "power_in"))
      (node (ref "U2") (pin "30") (pinfunction "AOUT2_30") (pintype "output"))
    )
    (net (code "31") (name "AOUT2_3") (class "Default")
      (node (ref "MOTOR3") (pin "3") (pinfunction "3_3") (pintype "bidirectional"))
      (node (ref "U$11") (pin "D1_1") (pinfunction "D1*1_D1_1") (pintype "power_in"))
      (node (ref "U$11") (pin "D1_2") (pinfunction "D1*2_D1_2") (pintype "power_in"))
      (node (ref "U$11") (pin "S2") (pinfunction "S2_S2") (pintype "power_in"))
      (node (ref "U3") (pin "30") (pinfunction "AOUT2_30") (pintype "output"))
    )
    (net (code "32") (name "AOUT2_4") (class "Default")
      (node (ref "MOTOR5") (pin "3") (pinfunction "3_3") (pintype "bidirectional"))
      (node (ref "U$15") (pin "D1_1") (pinfunction "D1*1_D1_1") (pintype "power_in"))
      (node (ref "U$15") (pin "D1_2") (pinfunction "D1*2_D1_2") (pintype "power_in"))
      (node (ref "U$15") (pin "S2") (pinfunction "S2_S2") (pintype "power_in"))
      (node (ref "U4") (pin "30") (pinfunction "AOUT2_30") (pintype "output"))
    )
    (net (code "33") (name "B1HS_1") (class "Default")
      (node (ref "U$2") (pin "G1") (pinfunction "G1_G1") (pintype "power_in"))
      (node (ref "U1") (pin "27") (pinfunction "B1HS_27") (pintype "output"))
    )
    (net (code "34") (name "B1HS_2") (class "Default")
      (node (ref "U$6") (pin "G1") (pinfunction "G1_G1") (pintype "power_in"))
      (node (ref "U2") (pin "27") (pinfunction "B1HS_27") (pintype "output"))
    )
    (net (code "35") (name "B1HS_3") (class "Default")
      (node (ref "U$10") (pin "G1") (pinfunction "G1_G1") (pintype "power_in"))
      (node (ref "U3") (pin "27") (pinfunction "B1HS_27") (pintype "output"))
    )
    (net (code "36") (name "B1HS_4") (class "Default")
      (node (ref "U$14") (pin "G1") (pinfunction "G1_G1") (pintype "power_in"))
      (node (ref "U4") (pin "27") (pinfunction "B1HS_27") (pintype "output"))
    )
    (net (code "37") (name "B1LS_1") (class "Default")
      (node (ref "U$2") (pin "G2") (pinfunction "G2_G2") (pintype "power_in"))
      (node (ref "U1") (pin "26") (pinfunction "B1LS_26") (pintype "output"))
    )
    (net (code "38") (name "B1LS_2") (class "Default")
      (node (ref "U$6") (pin "G2") (pinfunction "G2_G2") (pintype "power_in"))
      (node (ref "U2") (pin "26") (pinfunction "B1LS_26") (pintype "output"))
    )
    (net (code "39") (name "B1LS_3") (class "Default")
      (node (ref "U$10") (pin "G2") (pinfunction "G2_G2") (pintype "power_in"))
      (node (ref "U3") (pin "26") (pinfunction "B1LS_26") (pintype "output"))
    )
    (net (code "40") (name "B1LS_4") (class "Default")
      (node (ref "U$14") (pin "G2") (pinfunction "G2_G2") (pintype "power_in"))
      (node (ref "U4") (pin "26") (pinfunction "B1LS_26") (pintype "output"))
    )
    (net (code "41") (name "B2HS_1") (class "Default")
      (node (ref "U$4") (pin "G2") (pinfunction "G2_G2") (pintype "power_in"))
      (node (ref "U1") (pin "22") (pinfunction "B2HS_22") (pintype "output"))
    )
    (net (code "42") (name "B2HS_2") (class "Default")
      (node (ref "U$8") (pin "G2") (pinfunction "G2_G2") (pintype "power_in"))
      (node (ref "U2") (pin "22") (pinfunction "B2HS_22") (pintype "output"))
    )
    (net (code "43") (name "B2HS_3") (class "Default")
      (node (ref "U$12") (pin "G2") (pinfunction "G2_G2") (pintype "power_in"))
      (node (ref "U3") (pin "22") (pinfunction "B2HS_22") (pintype "output"))
    )
    (net (code "44") (name "B2HS_4") (class "Default")
      (node (ref "U$16") (pin "G2") (pinfunction "G2_G2") (pintype "power_in"))
      (node (ref "U4") (pin "22") (pinfunction "B2HS_22") (pintype "output"))
    )
    (net (code "45") (name "B2LS_1") (class "Default")
      (node (ref "U$4") (pin "G1") (pinfunction "G1_G1") (pintype "power_in"))
      (node (ref "U1") (pin "23") (pinfunction "B2LS_23") (pintype "output"))
    )
    (net (code "46") (name "B2LS_2") (class "Default")
      (node (ref "U$8") (pin "G1") (pinfunction "G1_G1") (pintype "power_in"))
      (node (ref "U2") (pin "23") (pinfunction "B2LS_23") (pintype "output"))
    )
    (net (code "47") (name "B2LS_3") (class "Default")
      (node (ref "U$12") (pin "G1") (pinfunction "G1_G1") (pintype "power_in"))
      (node (ref "U3") (pin "23") (pinfunction "B2LS_23") (pintype "output"))
    )
    (net (code "48") (name "B2LS_4") (class "Default")
      (node (ref "U$16") (pin "G1") (pinfunction "G1_G1") (pintype "power_in"))
      (node (ref "U4") (pin "23") (pinfunction "B2LS_23") (pintype "output"))
    )
    (net (code "49") (name "BEMF_1") (class "Default")
      (node (ref "TIC7") (pin "1") (pinfunction "1_1") (pintype "passive"))
      (node (ref "U1") (pin "20") (pinfunction "BEMF_20") (pintype "output"))
    )
    (net (code "50") (name "BEMF_2") (class "Default")
      (node (ref "TIC14") (pin "1") (pinfunction "1_1") (pintype "passive"))
      (node (ref "U2") (pin "20") (pinfunction "BEMF_20") (pintype "output"))
    )
    (net (code "51") (name "BEMF_3") (class "Default")
      (node (ref "TIC22") (pin "1") (pinfunction "1_1") (pintype "passive"))
      (node (ref "U3") (pin "20") (pinfunction "BEMF_20") (pintype "output"))
    )
    (net (code "52") (name "BEMF_4") (class "Default")
      (node (ref "TIC30") (pin "1") (pinfunction "1_1") (pintype "passive"))
      (node (ref "U4") (pin "20") (pinfunction "BEMF_20") (pintype "output"))
    )
    (net (code "53") (name "BIN1") (class "Default")
      (node (ref "U1") (pin "12") (pinfunction "BIN1_12") (pintype "input"))
    )
    (net (code "54") (name "BIN1.2") (class "Default")
      (node (ref "U2") (pin "12") (pinfunction "BIN1_12") (pintype "input"))
    )
    (net (code "55") (name "BIN1.3") (class "Default")
      (node (ref "U3") (pin "12") (pinfunction "BIN1_12") (pintype "input"))
    )
    (net (code "56") (name "BIN1.4") (class "Default")
      (node (ref "U4") (pin "12") (pinfunction "BIN1_12") (pintype "input"))
    )
    (net (code "57") (name "BIN2") (class "Default")
      (node (ref "U1") (pin "13") (pinfunction "BIN2_13") (pintype "input"))
    )
    (net (code "58") (name "BIN2.2") (class "Default")
      (node (ref "U2") (pin "13") (pinfunction "BIN2_13") (pintype "input"))
    )
    (net (code "59") (name "BIN2.3") (class "Default")
      (node (ref "U3") (pin "13") (pinfunction "BIN2_13") (pintype "input"))
    )
    (net (code "60") (name "BIN2.4") (class "Default")
      (node (ref "U4") (pin "13") (pinfunction "BIN2_13") (pintype "input"))
    )
    (net (code "61") (name "BISENN_1") (class "Default")
      (node (ref "SJ4") (pin "1") (pinfunction "1_1") (pintype "passive"))
      (node (ref "U1") (pin "24") (pinfunction "BISENN_24") (pintype "input"))
    )
    (net (code "62") (name "BISENN_2") (class "Default")
      (node (ref "SJ8") (pin "1") (pinfunction "1_1") (pintype "passive"))
      (node (ref "U2") (pin "24") (pinfunction "BISENN_24") (pintype "input"))
    )
    (net (code "63") (name "BISENN_3") (class "Default")
      (node (ref "SJ12") (pin "1") (pinfunction "1_1") (pintype "passive"))
      (node (ref "U3") (pin "24") (pinfunction "BISENN_24") (pintype "input"))
    )
    (net (code "64") (name "BISENN_4") (class "Default")
      (node (ref "SJ16") (pin "1") (pinfunction "1_1") (pintype "passive"))
      (node (ref "U4") (pin "24") (pinfunction "BISENN_24") (pintype "input"))
    )
    (net (code "65") (name "BISENP_1") (class "Default")
      (node (ref "SJ3") (pin "1") (pinfunction "1_1") (pintype "passive"))
      (node (ref "U1") (pin "25") (pinfunction "BISENP_25") (pintype "input"))
    )
    (net (code "66") (name "BISENP_2") (class "Default")
      (node (ref "SJ7") (pin "1") (pinfunction "1_1") (pintype "passive"))
      (node (ref "U2") (pin "25") (pinfunction "BISENP_25") (pintype "input"))
    )
    (net (code "67") (name "BISENP_3") (class "Default")
      (node (ref "SJ11") (pin "1") (pinfunction "1_1") (pintype "passive"))
      (node (ref "U3") (pin "25") (pinfunction "BISENP_25") (pintype "input"))
    )
    (net (code "68") (name "BISENP_4") (class "Default")
      (node (ref "SJ15") (pin "1") (pinfunction "1_1") (pintype "passive"))
      (node (ref "U4") (pin "25") (pinfunction "BISENP_25") (pintype "input"))
    )
    (net (code "69") (name "BOUT1_1") (class "Default")
      (node (ref "MOTOR1") (pin "2") (pinfunction "2_2") (pintype "bidirectional"))
      (node (ref "U$2") (pin "D22") (pinfunction "D2*2_D22") (pintype "power_in"))
      (node (ref "U$2") (pin "D2_1") (pinfunction "D2*1_D2_1") (pintype "power_in"))
      (node (ref "U$2") (pin "S1") (pinfunction "S1_S1") (pintype "power_in"))
      (node (ref "U1") (pin "28") (pinfunction "BOUT1_28") (pintype "output"))
    )
    (net (code "70") (name "BOUT1_2") (class "Default")
      (node (ref "MOTOR2") (pin "2") (pinfunction "2_2") (pintype "bidirectional"))
      (node (ref "U$6") (pin "D22") (pinfunction "D2*2_D22") (pintype "power_in"))
      (node (ref "U$6") (pin "D2_1") (pinfunction "D2*1_D2_1") (pintype "power_in"))
      (node (ref "U$6") (pin "S1") (pinfunction "S1_S1") (pintype "power_in"))
      (node (ref "U2") (pin "28") (pinfunction "BOUT1_28") (pintype "output"))
    )
    (net (code "71") (name "BOUT1_3") (class "Default")
      (node (ref "MOTOR3") (pin "2") (pinfunction "2_2") (pintype "bidirectional"))
      (node (ref "U$10") (pin "D22") (pinfunction "D2*2_D22") (pintype "power_in"))
      (node (ref "U$10") (pin "D2_1") (pinfunction "D2*1_D2_1") (pintype "power_in"))
      (node (ref "U$10") (pin "S1") (pinfunction "S1_S1") (pintype "power_in"))
      (node (ref "U3") (pin "28") (pinfunction "BOUT1_28") (pintype "output"))
    )
    (net (code "72") (name "BOUT1_4") (class "Default")
      (node (ref "MOTOR5") (pin "2") (pinfunction "2_2") (pintype "bidirectional"))
      (node (ref "U$14") (pin "D22") (pinfunction "D2*2_D22") (pintype "power_in"))
      (node (ref "U$14") (pin "D2_1") (pinfunction "D2*1_D2_1") (pintype "power_in"))
      (node (ref "U$14") (pin "S1") (pinfunction "S1_S1") (pintype "power_in"))
      (node (ref "U4") (pin "28") (pinfunction "BOUT1_28") (pintype "output"))
    )
    (net (code "73") (name "BOUT2_1") (class "Default")
      (node (ref "MOTOR1") (pin "1") (pinfunction "1_1") (pintype "bidirectional"))
      (node (ref "U$4") (pin "D1_1") (pinfunction "D1*1_D1_1") (pintype "power_in"))
      (node (ref "U$4") (pin "D1_2") (pinfunction "D1*2_D1_2") (pintype "power_in"))
      (node (ref "U$4") (pin "S2") (pinfunction "S2_S2") (pintype "power_in"))
      (node (ref "U1") (pin "21") (pinfunction "BOUT2_21") (pintype "output"))
    )
    (net (code "74") (name "BOUT2_2") (class "Default")
      (node (ref "MOTOR2") (pin "1") (pinfunction "1_1") (pintype "bidirectional"))
      (node (ref "U$8") (pin "D1_1") (pinfunction "D1*1_D1_1") (pintype "power_in"))
      (node (ref "U$8") (pin "D1_2") (pinfunction "D1*2_D1_2") (pintype "power_in"))
      (node (ref "U$8") (pin "S2") (pinfunction "S2_S2") (pintype "power_in"))
      (node (ref "U2") (pin "21") (pinfunction "BOUT2_21") (pintype "output"))
    )
    (net (code "75") (name "BOUT2_3") (class "Default")
      (node (ref "MOTOR3") (pin "1") (pinfunction "1_1") (pintype "bidirectional"))
      (node (ref "U$12") (pin "D1_1") (pinfunction "D1*1_D1_1") (pintype "power_in"))
      (node (ref "U$12") (pin "D1_2") (pinfunction "D1*2_D1_2") (pintype "power_in"))
      (node (ref "U$12") (pin "S2") (pinfunction "S2_S2") (pintype "power_in"))
      (node (ref "U3") (pin "21") (pinfunction "BOUT2_21") (pintype "output"))
    )
    (net (code "76") (name "BOUT2_4") (class "Default")
      (node (ref "MOTOR5") (pin "1") (pinfunction "1_1") (pintype "bidirectional"))
      (node (ref "U$16") (pin "D1_1") (pinfunction "D1*1_D1_1") (pintype "power_in"))
      (node (ref "U$16") (pin "D1_2") (pinfunction "D1*2_D1_2") (pintype "power_in"))
      (node (ref "U$16") (pin "S2") (pinfunction "S2_S2") (pintype "power_in"))
      (node (ref "U4") (pin "21") (pinfunction "BOUT2_21") (pintype "output"))
    )
    (net (code "77") (name "DIR1") (class "Default")
      (node (ref "JP2") (pin "13") (pinfunction "13_13") (pintype "passive"))
      (node (ref "SJ17") (pin "1") (pinfunction "1_1") (pintype "passive"))
      (node (ref "SJ18") (pin "1") (pinfunction "1_1") (pintype "passive"))
      (node (ref "SJ18") (pin "2") (pinfunction "2_2") (pintype "passive"))
      (node (ref "U1") (pin "11") (pinfunction "DIR_AIN2_11") (pintype "input"))
    )
    (net (code "78") (name "DIR1_STACK2") (class "Default")
      (node (ref "JP2") (pin "14") (pinfunction "14_14") (pintype "passive"))
      (node (ref "SJ17") (pin "2") (pinfunction "2_2") (pintype "passive"))
    )
    (net (code "79") (name "DIR2") (class "Default")
      (node (ref "JP2") (pin "9") (pinfunction "9_9") (pintype "passive"))
      (node (ref "SJ19") (pin "1") (pinfunction "1_1") (pintype "passive"))
      (node (ref "SJ20") (pin "1") (pinfunction "1_1") (pintype "passive"))
      (node (ref "SJ20") (pin "2") (pinfunction "2_2") (pintype "passive"))
      (node (ref "U2") (pin "11") (pinfunction "DIR_AIN2_11") (pintype "input"))
    )
    (net (code "80") (name "DIR2_STACK2") (class "Default")
      (node (ref "JP2") (pin "10") (pinfunction "10_10") (pintype "passive"))
      (node (ref "SJ19") (pin "2") (pinfunction "2_2") (pintype "passive"))
    )
    (net (code "81") (name "DIR3") (class "Default")
      (node (ref "JP2") (pin "5") (pinfunction "5_5") (pintype "passive"))
      (node (ref "SJ21") (pin "1") (pinfunction "1_1") (pintype "passive"))
      (node (ref "SJ22") (pin "1") (pinfunction "1_1") (pintype "passive"))
      (node (ref "SJ22") (pin "2") (pinfunction "2_2") (pintype "passive"))
      (node (ref "U3") (pin "11") (pinfunction "DIR_AIN2_11") (pintype "input"))
    )
    (net (code "82") (name "DIR3_STACK2") (class "Default")
      (node (ref "JP2") (pin "6") (pinfunction "6_6") (pintype "passive"))
      (node (ref "SJ21") (pin "2") (pinfunction "2_2") (pintype "passive"))
    )
    (net (code "83") (name "DIR4") (class "Default")
      (node (ref "JP2") (pin "1") (pinfunction "1_1") (pintype "passive"))
      (node (ref "SJ23") (pin "1") (pinfunction "1_1") (pintype "passive"))
      (node (ref "SJ24") (pin "1") (pinfunction "1_1") (pintype "passive"))
      (node (ref "SJ24") (pin "2") (pinfunction "2_2") (pintype "passive"))
      (node (ref "U4") (pin "11") (pinfunction "DIR_AIN2_11") (pintype "input"))
    )
    (net (code "84") (name "DIR4_STACK2") (class "Default")
      (node (ref "JP2") (pin "2") (pinfunction "2_2") (pintype "passive"))
      (node (ref "SJ23") (pin "2") (pinfunction "2_2") (pintype "passive"))
    )
    (net (code "85") (name "GND") (class "Default")
      (node (ref "JP2") (pin "21") (pinfunction "21_21") (pintype "passive"))
      (node (ref "JP2") (pin "22") (pinfunction "22_22") (pintype "passive"))
      (node (ref "JP2") (pin "23") (pinfunction "23_23") (pintype "passive"))
      (node (ref "JP2") (pin "24") (pinfunction "24_24") (pintype "passive"))
      (node (ref "JP2") (pin "25") (pinfunction "25_25") (pintype "passive"))
      (node (ref "JP2") (pin "26") (pinfunction "26_26") (pintype "passive"))
      (node (ref "JP2") (pin "27") (pinfunction "27_27") (pintype "passive"))
      (node (ref "JP2") (pin "28") (pinfunction "28_28") (pintype "passive"))
      (node (ref "JP3") (pin "11") (pinfunction "11_11") (pintype "passive"))
      (node (ref "JP3") (pin "13") (pinfunction "13_13") (pintype "passive"))
      (node (ref "JP3") (pin "15") (pinfunction "15_15") (pintype "passive"))
      (node (ref "JP3") (pin "17") (pinfunction "17_17") (pintype "passive"))
      (node (ref "JP3") (pin "19") (pinfunction "19_19") (pintype "passive"))
      (node (ref "JP3") (pin "9") (pinfunction "9_9") (pintype "passive"))
      (node (ref "R1") (pin "1") (pinfunction "1_1") (pintype "passive"))
      (node (ref "R2") (pin "1") (pinfunction "1_1") (pintype "passive"))
      (node (ref "R3") (pin "1") (pinfunction "1_1") (pintype "passive"))
      (node (ref "R4") (pin "1") (pinfunction "1_1") (pintype "passive"))
      (node (ref "R5") (pin "1") (pinfunction "1_1") (pintype "passive"))
      (node (ref "R6") (pin "1") (pinfunction "1_1") (pintype "passive"))
      (node (ref "R7") (pin "1") (pinfunction "1_1") (pintype "passive"))
      (node (ref "R8") (pin "1") (pinfunction "1_1") (pintype "passive"))
      (node (ref "SJ1") (pin "2") (pinfunction "2_2") (pintype "passive"))
      (node (ref "SJ12") (pin "2") (pinfunction "2_2") (pintype "passive"))
      (node (ref "SJ13") (pin "2") (pinfunction "2_2") (pintype "passive"))
      (node (ref "SJ16") (pin "2") (pinfunction "2_2") (pintype "passive"))
      (node (ref "SJ4") (pin "2") (pinfunction "2_2") (pintype "passive"))
      (node (ref "SJ5") (pin "2") (pinfunction "2_2") (pintype "passive"))
      (node (ref "SJ8") (pin "2") (pinfunction "2_2") (pintype "passive"))
      (node (ref "SJ9") (pin "2") (pinfunction "2_2") (pintype "passive"))
      (node (ref "TIC1") (pin "-") (pinfunction "-_-") (pintype "passive"))
      (node (ref "TIC11") (pin "1") (pinfunction "1_1") (pintype "passive"))
      (node (ref "TIC12") (pin "1") (pinfunction "1_1") (pintype "passive"))
      (node (ref "TIC13") (pin "1") (pinfunction "1_1") (pintype "passive"))
      (node (ref "TIC14") (pin "2") (pinfunction "2_2") (pintype "passive"))
      (node (ref "TIC15") (pin "-") (pinfunction "-_-") (pintype "passive"))
      (node (ref "TIC16") (pin "1") (pinfunction "1_1") (pintype "passive"))
      (node (ref "TIC19") (pin "1") (pinfunction "1_1") (pintype "passive"))
      (node (ref "TIC2") (pin "1") (pinfunction "1_1") (pintype "passive"))
      (node (ref "TIC20") (pin "1") (pinfunction "1_1") (pintype "passive"))
      (node (ref "TIC21") (pin "1") (pinfunction "1_1") (pintype "passive"))
      (node (ref "TIC22") (pin "2") (pinfunction "2_2") (pintype "passive"))
      (node (ref "TIC23") (pin "-") (pinfunction "-_-") (pintype "passive"))
      (node (ref "TIC24") (pin "1") (pinfunction "1_1") (pintype "passive"))
      (node (ref "TIC27") (pin "1") (pinfunction "1_1") (pintype "passive"))
      (node (ref "TIC28") (pin "1") (pinfunction "1_1") (pintype "passive"))
      (node (ref "TIC29") (pin "1") (pinfunction "1_1") (pintype "passive"))
      (node (ref "TIC30") (pin "2") (pinfunction "2_2") (pintype "passive"))
      (node (ref "TIC31") (pin "-") (pinfunction "-_-") (pintype "passive"))
      (node (ref "TIC32") (pin "1") (pinfunction "1_1") (pintype "passive"))
      (node (ref "TIC33") (pin "-") (pinfunction "-_-") (pintype "passive"))
      (node (ref "TIC5") (pin "1") (pinfunction "1_1") (pintype "passive"))
      (node (ref "TIC6") (pin "1") (pinfunction "1_1") (pintype "passive"))
      (node (ref "TIC7") (pin "2") (pinfunction "2_2") (pintype "passive"))
      (node (ref "TIC8") (pin "1") (pinfunction "1_1") (pintype "passive"))
      (node (ref "U$17") (pin "3") (pinfunction "SOURCE_3") (pintype "bidirectional"))
      (node (ref "U1") (pin "29") (pinfunction "GND_3_29") (pintype "power_in"))
      (node (ref "U1") (pin "38") (pinfunction "GND_38") (pintype "power_in"))
      (node (ref "U1") (pin "39") (pinfunction "PAD_39") (pintype "power_in"))
      (node (ref "U1") (pin "5") (pinfunction "GND_2_5") (pintype "power_in"))
      (node (ref "U2") (pin "29") (pinfunction "GND_3_29") (pintype "power_in"))
      (node (ref "U2") (pin "38") (pinfunction "GND_38") (pintype "power_in"))
      (node (ref "U2") (pin "39") (pinfunction "PAD_39") (pintype "power_in"))
      (node (ref "U2") (pin "5") (pinfunction "GND_2_5") (pintype "power_in"))
      (node (ref "U3") (pin "29") (pinfunction "GND_3_29") (pintype "power_in"))
      (node (ref "U3") (pin "38") (pinfunction "GND_38") (pintype "power_in"))
      (node (ref "U3") (pin "39") (pinfunction "PAD_39") (pintype "power_in"))
      (node (ref "U3") (pin "5") (pinfunction "GND_2_5") (pintype "power_in"))
      (node (ref "U4") (pin "29") (pinfunction "GND_3_29") (pintype "power_in"))
      (node (ref "U4") (pin "38") (pinfunction "GND_38") (pintype "power_in"))
      (node (ref "U4") (pin "39") (pinfunction "PAD_39") (pintype "power_in"))
      (node (ref "U4") (pin "5") (pinfunction "GND_2_5") (pintype "power_in"))
      (node (ref "X1") (pin "4") (pinfunction "S_4") (pintype "passive"))
      (node (ref "X1") (pin "6") (pinfunction "S_6") (pintype "passive"))
    )
    (net (code "86") (name "GND-A_1") (class "Default")
      (node (ref "R2") (pin "2") (pinfunction "2_2") (pintype "passive"))
      (node (ref "SJ2") (pin "2") (pinfunction "2_2") (pintype "passive"))
      (node (ref "U$1") (pin "S2") (pinfunction "S2_S2") (pintype "power_in"))
      (node (ref "U$3") (pin "S1") (pinfunction "S1_S1") (pintype "power_in"))
    )
    (net (code "87") (name "GND-A_2") (class "Default")
      (node (ref "R4") (pin "2") (pinfunction "2_2") (pintype "passive"))
      (node (ref "SJ6") (pin "2") (pinfunction "2_2") (pintype "passive"))
      (node (ref "U$5") (pin "S2") (pinfunction "S2_S2") (pintype "power_in"))
      (node (ref "U$7") (pin "S1") (pinfunction "S1_S1") (pintype "power_in"))
    )
    (net (code "88") (name "GND-A_3") (class "Default")
      (node (ref "R6") (pin "2") (pinfunction "2_2") (pintype "passive"))
      (node (ref "SJ10") (pin "2") (pinfunction "2_2") (pintype "passive"))
      (node (ref "U$11") (pin "S1") (pinfunction "S1_S1") (pintype "power_in"))
      (node (ref "U$9") (pin "S2") (pinfunction "S2_S2") (pintype "power_in"))
    )
    (net (code "89") (name "GND-A_4") (class "Default")
      (node (ref "R8") (pin "2") (pinfunction "2_2") (pintype "passive"))
      (node (ref "SJ14") (pin "2") (pinfunction "2_2") (pintype "passive"))
      (node (ref "U$13") (pin "S2") (pinfunction "S2_S2") (pintype "power_in"))
      (node (ref "U$15") (pin "S1") (pinfunction "S1_S1") (pintype "power_in"))
    )
    (net (code "90") (name "GND-B_1") (class "Default")
      (node (ref "R1") (pin "2") (pinfunction "2_2") (pintype "passive"))
      (node (ref "SJ3") (pin "2") (pinfunction "2_2") (pintype "passive"))
      (node (ref "U$2") (pin "S2") (pinfunction "S2_S2") (pintype "power_in"))
      (node (ref "U$4") (pin "S1") (pinfunction "S1_S1") (pintype "power_in"))
    )
    (net (code "91") (name "GND-B_2") (class "Default")
      (node (ref "R3") (pin "2") (pinfunction "2_2") (pintype "passive"))
      (node (ref "SJ7") (pin "2") (pinfunction "2_2") (pintype "passive"))
      (node (ref "U$6") (pin "S2") (pinfunction "S2_S2") (pintype "power_in"))
      (node (ref "U$8") (pin "S1") (pinfunction "S1_S1") (pintype "power_in"))
    )
    (net (code "92") (name "GND-B_3") (class "Default")
      (node (ref "R5") (pin "2") (pinfunction "2_2") (pintype "passive"))
      (node (ref "SJ11") (pin "2") (pinfunction "2_2") (pintype "passive"))
      (node (ref "U$10") (pin "S2") (pinfunction "S2_S2") (pintype "power_in"))
      (node (ref "U$12") (pin "S1") (pinfunction "S1_S1") (pintype "power_in"))
    )
    (net (code "93") (name "GND-B_4") (class "Default")
      (node (ref "R7") (pin "2") (pinfunction "2_2") (pintype "passive"))
      (node (ref "SJ15") (pin "2") (pinfunction "2_2") (pintype "passive"))
      (node (ref "U$14") (pin "S2") (pinfunction "S2_S2") (pintype "power_in"))
      (node (ref "U$16") (pin "S1") (pinfunction "S1_S1") (pintype "power_in"))
    )
    (net (code "94") (name "MOSFET") (class "Default")
      (node (ref "JP3") (pin "22") (pinfunction "22_22") (pintype "passive"))
      (node (ref "R9") (pin "1") (pinfunction "1_1") (pintype "passive"))
    )
    (net (code "95") (name "MOSFETOUT") (class "Default")
      (node (ref "D10") (pin "A") (pinfunction "A_A") (pintype "passive"))
      (node (ref "U$17") (pin "2") (pinfunction "DRAIN_2") (pintype "bidirectional"))
      (node (ref "X3") (pin "1") (pinfunction "KL_1") (pintype "passive"))
    )
    (net (code "96") (name "Net-(FAULTLED-PadC)") (class "Default")
      (node (ref "FAULTLED") (pin "C") (pinfunction "C_C") (pintype "passive"))
      (node (ref "TIR4") (pin "1") (pinfunction "1_1") (pintype "passive"))
    )
    (net (code "97") (name "Net-(FAULTLED1-PadC)") (class "Default")
      (node (ref "FAULTLED1") (pin "C") (pinfunction "C_C") (pintype "passive"))
      (node (ref "TIR2") (pin "1") (pinfunction "1_1") (pintype "passive"))
    )
    (net (code "98") (name "Net-(FAULTLED2-PadC)") (class "Default")
      (node (ref "FAULTLED2") (pin "C") (pinfunction "C_C") (pintype "passive"))
      (node (ref "TIR8") (pin "1") (pinfunction "1_1") (pintype "passive"))
    )
    (net (code "99") (name "Net-(FAULTLED3-PadC)") (class "Default")
      (node (ref "FAULTLED3") (pin "C") (pinfunction "C_C") (pintype "passive"))
      (node (ref "TIR11") (pin "1") (pinfunction "1_1") (pintype "passive"))
    )
    (net (code "100") (name "Net-(STALLLED-PadC)") (class "Default")
      (node (ref "STALLLED") (pin "C") (pinfunction "C_C") (pintype "passive"))
      (node (ref "TIR5") (pin "1") (pinfunction "1_1") (pintype "passive"))
    )
    (net (code "101") (name "Net-(STALLLED1-PadC)") (class "Default")
      (node (ref "STALLLED1") (pin "C") (pinfunction "C_C") (pintype "passive"))
      (node (ref "TIR1") (pin "1") (pinfunction "1_1") (pintype "passive"))
    )
    (net (code "102") (name "Net-(STALLLED2-PadC)") (class "Default")
      (node (ref "STALLLED2") (pin "C") (pinfunction "C_C") (pintype "passive"))
      (node (ref "TIR7") (pin "1") (pinfunction "1_1") (pintype "passive"))
    )
    (net (code "103") (name "Net-(STALLLED3-PadC)") (class "Default")
      (node (ref "STALLLED3") (pin "C") (pinfunction "C_C") (pintype "passive"))
      (node (ref "TIR10") (pin "1") (pinfunction "1_1") (pintype "passive"))
    )
    (net (code "104") (name "Net-(U$17-GATE)") (class "Default")
      (node (ref "R9") (pin "2") (pinfunction "2_2") (pintype "passive"))
      (node (ref "U$17") (pin "1") (pinfunction "GATE_1") (pintype "bidirectional"))
    )
    (net (code "105") (name "Net-(U1-CP1)") (class "Default")
      (node (ref "TIC3") (pin "1") (pinfunction "1_1") (pintype "passive"))
      (node (ref "U1") (pin "1") (pinfunction "CP1_1") (pintype "passive"))
    )
    (net (code "106") (name "Net-(U1-CP2)") (class "Default")
      (node (ref "TIC3") (pin "2") (pinfunction "2_2") (pintype "passive"))
      (node (ref "U1") (pin "2") (pinfunction "CP2_2") (pintype "passive"))
    )
    (net (code "107") (name "Net-(U1-FAULT_N)") (class "Default")
      (node (ref "TIR4") (pin "2") (pinfunction "2_2") (pintype "passive"))
      (node (ref "U1") (pin "18") (pinfunction "FAULT_N_18") (pintype "open_collector"))
    )
    (net (code "108") (name "Net-(U1-STALL_BEMFV_N)") (class "Default")
      (node (ref "TIR5") (pin "2") (pinfunction "2_2") (pintype "passive"))
      (node (ref "U1") (pin "19") (pinfunction "STALL_BEMFV_N_19") (pintype "open_collector"))
    )
    (net (code "109") (name "Net-(U1-V5)") (class "Default")
      (node (ref "TIC5") (pin "2") (pinfunction "2_2") (pintype "passive"))
      (node (ref "U1") (pin "6") (pinfunction "V5_6") (pintype "power_in"))
    )
    (net (code "110") (name "Net-(U1-VCP)") (class "Default")
      (node (ref "TIC4") (pin "2") (pinfunction "2_2") (pintype "passive"))
      (node (ref "U1") (pin "3") (pinfunction "VCP_3") (pintype "passive"))
    )
    (net (code "111") (name "Net-(U1-VINT)") (class "Default")
      (node (ref "TIC6") (pin "2") (pinfunction "2_2") (pintype "passive"))
      (node (ref "U1") (pin "7") (pinfunction "VINT_7") (pintype "power_in"))
    )
    (net (code "112") (name "Net-(U2-CP1)") (class "Default")
      (node (ref "TIC9") (pin "1") (pinfunction "1_1") (pintype "passive"))
      (node (ref "U2") (pin "1") (pinfunction "CP1_1") (pintype "passive"))
    )
    (net (code "113") (name "Net-(U2-CP2)") (class "Default")
      (node (ref "TIC9") (pin "2") (pinfunction "2_2") (pintype "passive"))
      (node (ref "U2") (pin "2") (pinfunction "CP2_2") (pintype "passive"))
    )
    (net (code "114") (name "Net-(U2-FAULT_N)") (class "Default")
      (node (ref "TIR2") (pin "2") (pinfunction "2_2") (pintype "passive"))
      (node (ref "U2") (pin "18") (pinfunction "FAULT_N_18") (pintype "open_collector"))
    )
    (net (code "115") (name "Net-(U2-STALL_BEMFV_N)") (class "Default")
      (node (ref "TIR1") (pin "2") (pinfunction "2_2") (pintype "passive"))
      (node (ref "U2") (pin "19") (pinfunction "STALL_BEMFV_N_19") (pintype "open_collector"))
    )
    (net (code "116") (name "Net-(U2-V5)") (class "Default")
      (node (ref "TIC11") (pin "2") (pinfunction "2_2") (pintype "passive"))
      (node (ref "U2") (pin "6") (pinfunction "V5_6") (pintype "power_in"))
    )
    (net (code "117") (name "Net-(U2-VCP)") (class "Default")
      (node (ref "TIC10") (pin "2") (pinfunction "2_2") (pintype "passive"))
      (node (ref "U2") (pin "3") (pinfunction "VCP_3") (pintype "passive"))
    )
    (net (code "118") (name "Net-(U2-VINT)") (class "Default")
      (node (ref "TIC12") (pin "2") (pinfunction "2_2") (pintype "passive"))
      (node (ref "U2") (pin "7") (pinfunction "VINT_7") (pintype "power_in"))
    )
    (net (code "119") (name "Net-(U3-CP1)") (class "Default")
      (node (ref "TIC17") (pin "1") (pinfunction "1_1") (pintype "passive"))
      (node (ref "U3") (pin "1") (pinfunction "CP1_1") (pintype "passive"))
    )
    (net (code "120") (name "Net-(U3-CP2)") (class "Default")
      (node (ref "TIC17") (pin "2") (pinfunction "2_2") (pintype "passive"))
      (node (ref "U3") (pin "2") (pinfunction "CP2_2") (pintype "passive"))
    )
    (net (code "121") (name "Net-(U3-FAULT_N)") (class "Default")
      (node (ref "TIR8") (pin "2") (pinfunction "2_2") (pintype "passive"))
      (node (ref "U3") (pin "18") (pinfunction "FAULT_N_18") (pintype "open_collector"))
    )
    (net (code "122") (name "Net-(U3-STALL_BEMFV_N)") (class "Default")
      (node (ref "TIR7") (pin "2") (pinfunction "2_2") (pintype "passive"))
      (node (ref "U3") (pin "19") (pinfunction "STALL_BEMFV_N_19") (pintype "open_collector"))
    )
    (net (code "123") (name "Net-(U3-V5)") (class "Default")
      (node (ref "TIC19") (pin "2") (pinfunction "2_2") (pintype "passive"))
      (node (ref "U3") (pin "6") (pinfunction "V5_6") (pintype "power_in"))
    )
    (net (code "124") (name "Net-(U3-VCP)") (class "Default")
      (node (ref "TIC18") (pin "2") (pinfunction "2_2") (pintype "passive"))
      (node (ref "U3") (pin "3") (pinfunction "VCP_3") (pintype "passive"))
    )
    (net (code "125") (name "Net-(U3-VINT)") (class "Default")
      (node (ref "TIC20") (pin "2") (pinfunction "2_2") (pintype "passive"))
      (node (ref "U3") (pin "7") (pinfunction "VINT_7") (pintype "power_in"))
    )
    (net (code "126") (name "Net-(U4-CP1)") (class "Default")
      (node (ref "TIC25") (pin "1") (pinfunction "1_1") (pintype "passive"))
      (node (ref "U4") (pin "1") (pinfunction "CP1_1") (pintype "passive"))
    )
    (net (code "127") (name "Net-(U4-CP2)") (class "Default")
      (node (ref "TIC25") (pin "2") (pinfunction "2_2") (pintype "passive"))
      (node (ref "U4") (pin "2") (pinfunction "CP2_2") (pintype "passive"))
    )
    (net (code "128") (name "Net-(U4-FAULT_N)") (class "Default")
      (node (ref "TIR11") (pin "2") (pinfunction "2_2") (pintype "passive"))
      (node (ref "U4") (pin "18") (pinfunction "FAULT_N_18") (pintype "open_collector"))
    )
    (net (code "129") (name "Net-(U4-STALL_BEMFV_N)") (class "Default")
      (node (ref "TIR10") (pin "2") (pinfunction "2_2") (pintype "passive"))
      (node (ref "U4") (pin "19") (pinfunction "STALL_BEMFV_N_19") (pintype "open_collector"))
    )
    (net (code "130") (name "Net-(U4-V5)") (class "Default")
      (node (ref "TIC27") (pin "2") (pinfunction "2_2") (pintype "passive"))
      (node (ref "U4") (pin "6") (pinfunction "V5_6") (pintype "power_in"))
    )
    (net (code "131") (name "Net-(U4-VCP)") (class "Default")
      (node (ref "TIC26") (pin "2") (pinfunction "2_2") (pintype "passive"))
      (node (ref "U4") (pin "3") (pinfunction "VCP_3") (pintype "passive"))
    )
    (net (code "132") (name "Net-(U4-VINT)") (class "Default")
      (node (ref "TIC28") (pin "2") (pinfunction "2_2") (pintype "passive"))
      (node (ref "U4") (pin "7") (pinfunction "VINT_7") (pintype "power_in"))
    )
    (net (code "133") (name "PULLUPVCC") (class "Default")
      (node (ref "FAULTLED") (pin "A") (pinfunction "A_A") (pintype "passive"))
      (node (ref "FAULTLED1") (pin "A") (pinfunction "A_A") (pintype "passive"))
      (node (ref "FAULTLED2") (pin "A") (pinfunction "A_A") (pintype "passive"))
      (node (ref "FAULTLED3") (pin "A") (pinfunction "A_A") (pintype "passive"))
      (node (ref "JP3") (pin "20") (pinfunction "20_20") (pintype "passive"))
      (node (ref "STALLLED") (pin "A") (pinfunction "A_A") (pintype "passive"))
      (node (ref "STALLLED1") (pin "A") (pinfunction "A_A") (pintype "passive"))
      (node (ref "STALLLED2") (pin "A") (pinfunction "A_A") (pintype "passive"))
      (node (ref "STALLLED3") (pin "A") (pinfunction "A_A") (pintype "passive"))
      (node (ref "TIR12") (pin "1") (pinfunction "1_1") (pintype "passive"))
      (node (ref "TIR3") (pin "1") (pinfunction "1_1") (pintype "passive"))
      (node (ref "TIR6") (pin "1") (pinfunction "1_1") (pintype "passive"))
      (node (ref "TIR9") (pin "1") (pinfunction "1_1") (pintype "passive"))
    )
    (net (code "134") (name "RESET") (class "Default")
      (node (ref "JP2") (pin "19") (pinfunction "19_19") (pintype "passive"))
      (node (ref "JP3") (pin "12") (pinfunction "12_12") (pintype "passive"))
      (node (ref "U1") (pin "9") (pinfunction "RESET_9") (pintype "input"))
      (node (ref "U2") (pin "9") (pinfunction "RESET_9") (pintype "input"))
      (node (ref "U3") (pin "9") (pinfunction "RESET_9") (pintype "input"))
      (node (ref "U4") (pin "9") (pinfunction "RESET_9") (pintype "input"))
    )
    (net (code "135") (name "SCK") (class "Default")
      (node (ref "JP3") (pin "14") (pinfunction "14_14") (pintype "passive"))
      (node (ref "U1") (pin "14") (pinfunction "SCLK_14") (pintype "input"))
      (node (ref "U2") (pin "14") (pinfunction "SCLK_14") (pintype "input"))
      (node (ref "U3") (pin "14") (pinfunction "SCLK_14") (pintype "input"))
      (node (ref "U4") (pin "14") (pinfunction "SCLK_14") (pintype "input"))
    )
    (net (code "136") (name "SCS1") (class "Default")
      (node (ref "JP3") (pin "8") (pinfunction "8_8") (pintype "passive"))
      (node (ref "SJ33") (pin "1") (pinfunction "1_1") (pintype "passive"))
      (node (ref "SJ34") (pin "1") (pinfunction "1_1") (pintype "passive"))
      (node (ref "SJ34") (pin "2") (pinfunction "2_2") (pintype "passive"))
      (node (ref "U1") (pin "16") (pinfunction "SCS_16") (pintype "input"))
    )
    (net (code "137") (name "SCS2") (class "Default")
      (node (ref "JP3") (pin "6") (pinfunction "6_6") (pintype "passive"))
      (node (ref "SJ35") (pin "1") (pinfunction "1_1") (pintype "passive"))
      (node (ref "SJ36") (pin "1") (pinfunction "1_1") (pintype "passive"))
      (node (ref "SJ36") (pin "2") (pinfunction "2_2") (pintype "passive"))
      (node (ref "U2") (pin "16") (pinfunction "SCS_16") (pintype "input"))
    )
    (net (code "138") (name "SCS3") (class "Default")
      (node (ref "JP3") (pin "4") (pinfunction "4_4") (pintype "passive"))
      (node (ref "SJ37") (pin "1") (pinfunction "1_1") (pintype "passive"))
      (node (ref "SJ38") (pin "1") (pinfunction "1_1") (pintype "passive"))
      (node (ref "SJ38") (pin "2") (pinfunction "2_2") (pintype "passive"))
      (node (ref "U3") (pin "16") (pinfunction "SCS_16") (pintype "input"))
    )
    (net (code "139") (name "SCS4") (class "Default")
      (node (ref "JP3") (pin "2") (pinfunction "2_2") (pintype "passive"))
      (node (ref "SJ39") (pin "1") (pinfunction "1_1") (pintype "passive"))
      (node (ref "SJ40") (pin "1") (pinfunction "1_1") (pintype "passive"))
      (node (ref "SJ40") (pin "2") (pinfunction "2_2") (pintype "passive"))
      (node (ref "U4") (pin "16") (pinfunction "SCS_16") (pintype "input"))
    )
    (net (code "140") (name "SCS5") (class "Default")
      (node (ref "JP3") (pin "7") (pinfunction "7_7") (pintype "passive"))
      (node (ref "SJ33") (pin "2") (pinfunction "2_2") (pintype "passive"))
    )
    (net (code "141") (name "SCS6") (class "Default")
      (node (ref "JP3") (pin "5") (pinfunction "5_5") (pintype "passive"))
      (node (ref "SJ35") (pin "2") (pinfunction "2_2") (pintype "passive"))
    )
    (net (code "142") (name "SCS7") (class "Default")
      (node (ref "JP3") (pin "3") (pinfunction "3_3") (pintype "passive"))
      (node (ref "SJ37") (pin "2") (pinfunction "2_2") (pintype "passive"))
    )
    (net (code "143") (name "SCS8") (class "Default")
      (node (ref "JP3") (pin "1") (pinfunction "1_1") (pintype "passive"))
      (node (ref "SJ39") (pin "2") (pinfunction "2_2") (pintype "passive"))
    )
    (net (code "144") (name "SDATI") (class "Default")
      (node (ref "JP3") (pin "18") (pinfunction "18_18") (pintype "passive"))
      (node (ref "U1") (pin "15") (pinfunction "SDATI_15") (pintype "input"))
      (node (ref "U2") (pin "15") (pinfunction "SDATI_15") (pintype "input"))
      (node (ref "U3") (pin "15") (pinfunction "SDATI_15") (pintype "input"))
      (node (ref "U4") (pin "15") (pinfunction "SDATI_15") (pintype "input"))
    )
    (net (code "145") (name "SDATO1") (class "Default")
      (node (ref "JP3") (pin "16") (pinfunction "16_16") (pintype "passive"))
      (node (ref "TIR12") (pin "2") (pinfunction "2_2") (pintype "passive"))
      (node (ref "TIR3") (pin "2") (pinfunction "2_2") (pintype "passive"))
      (node (ref "TIR6") (pin "2") (pinfunction "2_2") (pintype "passive"))
      (node (ref "TIR9") (pin "2") (pinfunction "2_2") (pintype "passive"))
      (node (ref "U1") (pin "17") (pinfunction "SDATO_17") (pintype "open_collector"))
      (node (ref "U2") (pin "17") (pinfunction "SDATO_17") (pintype "open_collector"))
      (node (ref "U3") (pin "17") (pinfunction "SDATO_17") (pintype "open_collector"))
      (node (ref "U4") (pin "17") (pinfunction "SDATO_17") (pintype "open_collector"))
    )
    (net (code "146") (name "SLEEP") (class "Default")
      (node (ref "JP2") (pin "17") (pinfunction "17_17") (pintype "passive"))
      (node (ref "JP3") (pin "10") (pinfunction "10_10") (pintype "passive"))
      (node (ref "U1") (pin "8") (pinfunction "SLEEP_N_8") (pintype "input"))
      (node (ref "U2") (pin "8") (pinfunction "SLEEP_N_8") (pintype "input"))
      (node (ref "U3") (pin "8") (pinfunction "SLEEP_N_8") (pintype "input"))
      (node (ref "U4") (pin "8") (pinfunction "SLEEP_N_8") (pintype "input"))
    )
    (net (code "147") (name "STEP1") (class "Default")
      (node (ref "JP2") (pin "15") (pinfunction "15_15") (pintype "passive"))
      (node (ref "SJ25") (pin "1") (pinfunction "1_1") (pintype "passive"))
      (node (ref "SJ26") (pin "1") (pinfunction "1_1") (pintype "passive"))
      (node (ref "SJ26") (pin "2") (pinfunction "2_2") (pintype "passive"))
      (node (ref "U1") (pin "10") (pinfunction "STEP_AIN1_10") (pintype "input"))
    )
    (net (code "148") (name "STEP1_STACK2") (class "Default")
      (node (ref "JP2") (pin "16") (pinfunction "16_16") (pintype "passive"))
      (node (ref "SJ25") (pin "2") (pinfunction "2_2") (pintype "passive"))
    )
    (net (code "149") (name "STEP2") (class "Default")
      (node (ref "JP2") (pin "11") (pinfunction "11_11") (pintype "passive"))
      (node (ref "SJ27") (pin "1") (pinfunction "1_1") (pintype "passive"))
      (node (ref "SJ28") (pin "1") (pinfunction "1_1") (pintype "passive"))
      (node (ref "SJ28") (pin "2") (pinfunction "2_2") (pintype "passive"))
      (node (ref "U2") (pin "10") (pinfunction "STEP_AIN1_10") (pintype "input"))
    )
    (net (code "150") (name "STEP2_STACK2") (class "Default")
      (node (ref "JP2") (pin "12") (pinfunction "12_12") (pintype "passive"))
      (node (ref "SJ27") (pin "2") (pinfunction "2_2") (pintype "passive"))
    )
    (net (code "151") (name "STEP3") (class "Default")
      (node (ref "JP2") (pin "7") (pinfunction "7_7") (pintype "passive"))
      (node (ref "SJ29") (pin "1") (pinfunction "1_1") (pintype "passive"))
      (node (ref "SJ30") (pin "1") (pinfunction "1_1") (pintype "passive"))
      (node (ref "SJ30") (pin "2") (pinfunction "2_2") (pintype "passive"))
      (node (ref "U3") (pin "10") (pinfunction "STEP_AIN1_10") (pintype "input"))
    )
    (net (code "152") (name "STEP3_STACK2") (class "Default")
      (node (ref "JP2") (pin "8") (pinfunction "8_8") (pintype "passive"))
      (node (ref "SJ29") (pin "2") (pinfunction "2_2") (pintype "passive"))
    )
    (net (code "153") (name "STEP4") (class "Default")
      (node (ref "JP2") (pin "3") (pinfunction "3_3") (pintype "passive"))
      (node (ref "SJ31") (pin "1") (pinfunction "1_1") (pintype "passive"))
      (node (ref "SJ32") (pin "1") (pinfunction "1_1") (pintype "passive"))
      (node (ref "SJ32") (pin "2") (pinfunction "2_2") (pintype "passive"))
      (node (ref "U4") (pin "10") (pinfunction "STEP_AIN1_10") (pintype "input"))
    )
    (net (code "154") (name "STEP4_STACK2") (class "Default")
      (node (ref "JP2") (pin "4") (pinfunction "4_4") (pintype "passive"))
      (node (ref "SJ31") (pin "2") (pinfunction "2_2") (pintype "passive"))
    )
    (net (code "155") (name "VCC") (class "Default")
      (node (ref "JP3") (pin "23") (pinfunction "23_23") (pintype "passive"))
      (node (ref "JP3") (pin "24") (pinfunction "24_24") (pintype "passive"))
      (node (ref "JP3") (pin "25") (pinfunction "25_25") (pintype "passive"))
      (node (ref "JP3") (pin "26") (pinfunction "26_26") (pintype "passive"))
      (node (ref "JP3") (pin "27") (pinfunction "27_27") (pintype "passive"))
      (node (ref "JP3") (pin "28") (pinfunction "28_28") (pintype "passive"))
      (node (ref "X1") (pin "5") (pinfunction "S_5") (pintype "passive"))
    )
    (net (code "156") (name "VM") (class "Default")
      (node (ref "D10") (pin "C") (pinfunction "C_C") (pintype "passive"))
      (node (ref "JP1") (pin "1") (pinfunction "1_1") (pintype "passive"))
      (node (ref "JP1") (pin "2") (pinfunction "2_2") (pintype "passive"))
      (node (ref "JP1") (pin "3") (pinfunction "3_3") (pintype "passive"))
      (node (ref "JP1") (pin "4") (pinfunction "4_4") (pintype "passive"))
      (node (ref "JP4") (pin "1") (pinfunction "1_1") (pintype "passive"))
      (node (ref "JP4") (pin "2") (pinfunction "2_2") (pintype "passive"))
      (node (ref "JP4") (pin "3") (pinfunction "3_3") (pintype "passive"))
      (node (ref "JP4") (pin "4") (pinfunction "4_4") (pintype "passive"))
      (node (ref "TIC1") (pin "+") (pinfunction "+_+") (pintype "passive"))
      (node (ref "TIC10") (pin "1") (pinfunction "1_1") (pintype "passive"))
      (node (ref "TIC13") (pin "2") (pinfunction "2_2") (pintype "passive"))
      (node (ref "TIC15") (pin "+") (pinfunction "+_+") (pintype "passive"))
      (node (ref "TIC16") (pin "2") (pinfunction "2_2") (pintype "passive"))
      (node (ref "TIC18") (pin "1") (pinfunction "1_1") (pintype "passive"))
      (node (ref "TIC2") (pin "2") (pinfunction "2_2") (pintype "passive"))
      (node (ref "TIC21") (pin "2") (pinfunction "2_2") (pintype "passive"))
      (node (ref "TIC23") (pin "+") (pinfunction "+_+") (pintype "passive"))
      (node (ref "TIC24") (pin "2") (pinfunction "2_2") (pintype "passive"))
      (node (ref "TIC26") (pin "1") (pinfunction "1_1") (pintype "passive"))
      (node (ref "TIC29") (pin "2") (pinfunction "2_2") (pintype "passive"))
      (node (ref "TIC31") (pin "+") (pinfunction "+_+") (pintype "passive"))
      (node (ref "TIC32") (pin "2") (pinfunction "2_2") (pintype "passive"))
      (node (ref "TIC33") (pin "+") (pinfunction "+_+") (pintype "passive"))
      (node (ref "TIC4") (pin "1") (pinfunction "1_1") (pintype "passive"))
      (node (ref "TIC8") (pin "2") (pinfunction "2_2") (pintype "passive"))
      (node (ref "U$1") (pin "D1_1") (pinfunction "D1*1_D1_1") (pintype "power_in"))
      (node (ref "U$1") (pin "D1_2") (pinfunction "D1*2_D1_2") (pintype "power_in"))
      (node (ref "U$10") (pin "D1_1") (pinfunction "D1*1_D1_1") (pintype "power_in"))
      (node (ref "U$10") (pin "D1_2") (pinfunction "D1*2_D1_2") (pintype "power_in"))
      (node (ref "U$11") (pin "D22") (pinfunction "D2*2_D22") (pintype "power_in"))
      (node (ref "U$11") (pin "D2_1") (pinfunction "D2*1_D2_1") (pintype "power_in"))
      (node (ref "U$12") (pin "D22") (pinfunction "D2*2_D22") (pintype "power_in"))
      (node (ref "U$12") (pin "D2_1") (pinfunction "D2*1_D2_1") (pintype "power_in"))
      (node (ref "U$13") (pin "D1_1") (pinfunction "D1*1_D1_1") (pintype "power_in"))
      (node (ref "U$13") (pin "D1_2") (pinfunction "D1*2_D1_2") (pintype "power_in"))
      (node (ref "U$14") (pin "D1_1") (pinfunction "D1*1_D1_1") (pintype "power_in"))
      (node (ref "U$14") (pin "D1_2") (pinfunction "D1*2_D1_2") (pintype "power_in"))
      (node (ref "U$15") (pin "D22") (pinfunction "D2*2_D22") (pintype "power_in"))
      (node (ref "U$15") (pin "D2_1") (pinfunction "D2*1_D2_1") (pintype "power_in"))
      (node (ref "U$16") (pin "D22") (pinfunction "D2*2_D22") (pintype "power_in"))
      (node (ref "U$16") (pin "D2_1") (pinfunction "D2*1_D2_1") (pintype "power_in"))
      (node (ref "U$2") (pin "D1_1") (pinfunction "D1*1_D1_1") (pintype "power_in"))
      (node (ref "U$2") (pin "D1_2") (pinfunction "D1*2_D1_2") (pintype "power_in"))
      (node (ref "U$3") (pin "D22") (pinfunction "D2*2_D22") (pintype "power_in"))
      (node (ref "U$3") (pin "D2_1") (pinfunction "D2*1_D2_1") (pintype "power_in"))
      (node (ref "U$4") (pin "D22") (pinfunction "D2*2_D22") (pintype "power_in"))
      (node (ref "U$4") (pin "D2_1") (pinfunction "D2*1_D2_1") (pintype "power_in"))
      (node (ref "U$5") (pin "D1_1") (pinfunction "D1*1_D1_1") (pintype "power_in"))
      (node (ref "U$5") (pin "D1_2") (pinfunction "D1*2_D1_2") (pintype "power_in"))
      (node (ref "U$6") (pin "D1_1") (pinfunction "D1*1_D1_1") (pintype "power_in"))
      (node (ref "U$6") (pin "D1_2") (pinfunction "D1*2_D1_2") (pintype "power_in"))
      (node (ref "U$7") (pin "D22") (pinfunction "D2*2_D22") (pintype "power_in"))
      (node (ref "U$7") (pin "D2_1") (pinfunction "D2*1_D2_1") (pintype "power_in"))
      (node (ref "U$8") (pin "D22") (pinfunction "D2*2_D22") (pintype "power_in"))
      (node (ref "U$8") (pin "D2_1") (pinfunction "D2*1_D2_1") (pintype "power_in"))
      (node (ref "U$9") (pin "D1_1") (pinfunction "D1*1_D1_1") (pintype "power_in"))
      (node (ref "U$9") (pin "D1_2") (pinfunction "D1*2_D1_2") (pintype "power_in"))
      (node (ref "U1") (pin "4") (pinfunction "VM_4") (pintype "power_in"))
      (node (ref "U2") (pin "4") (pinfunction "VM_4") (pintype "power_in"))
      (node (ref "U3") (pin "4") (pinfunction "VM_4") (pintype "power_in"))
      (node (ref "U4") (pin "4") (pinfunction "VM_4") (pintype "power_in"))
      (node (ref "X1") (pin "1") (pinfunction "S_1") (pintype "passive"))
      (node (ref "X1") (pin "2") (pinfunction "S_2") (pintype "passive"))
      (node (ref "X1") (pin "3") (pinfunction "S_3") (pintype "passive"))
      (node (ref "X3") (pin "2") (pinfunction "KL_2") (pintype "passive"))
    )
    (net (code "157") (name "unconnected-(JP2-Pad18)") (class "Default")
      (node (ref "JP2") (pin "18") (pinfunction "18_18") (pintype "passive"))
    )
    (net (code "158") (name "unconnected-(JP2-Pad20)") (class "Default")
      (node (ref "JP2") (pin "20") (pinfunction "20_20") (pintype "passive"))
    )
    (net (code "159") (name "unconnected-(JP3-Pad21)") (class "Default")
      (node (ref "JP3") (pin "21") (pinfunction "21_21") (pintype "passive"))
    )
  )
)
